# STM32F103.net
KiCad netlist of a schematic drawn in Altium Designer
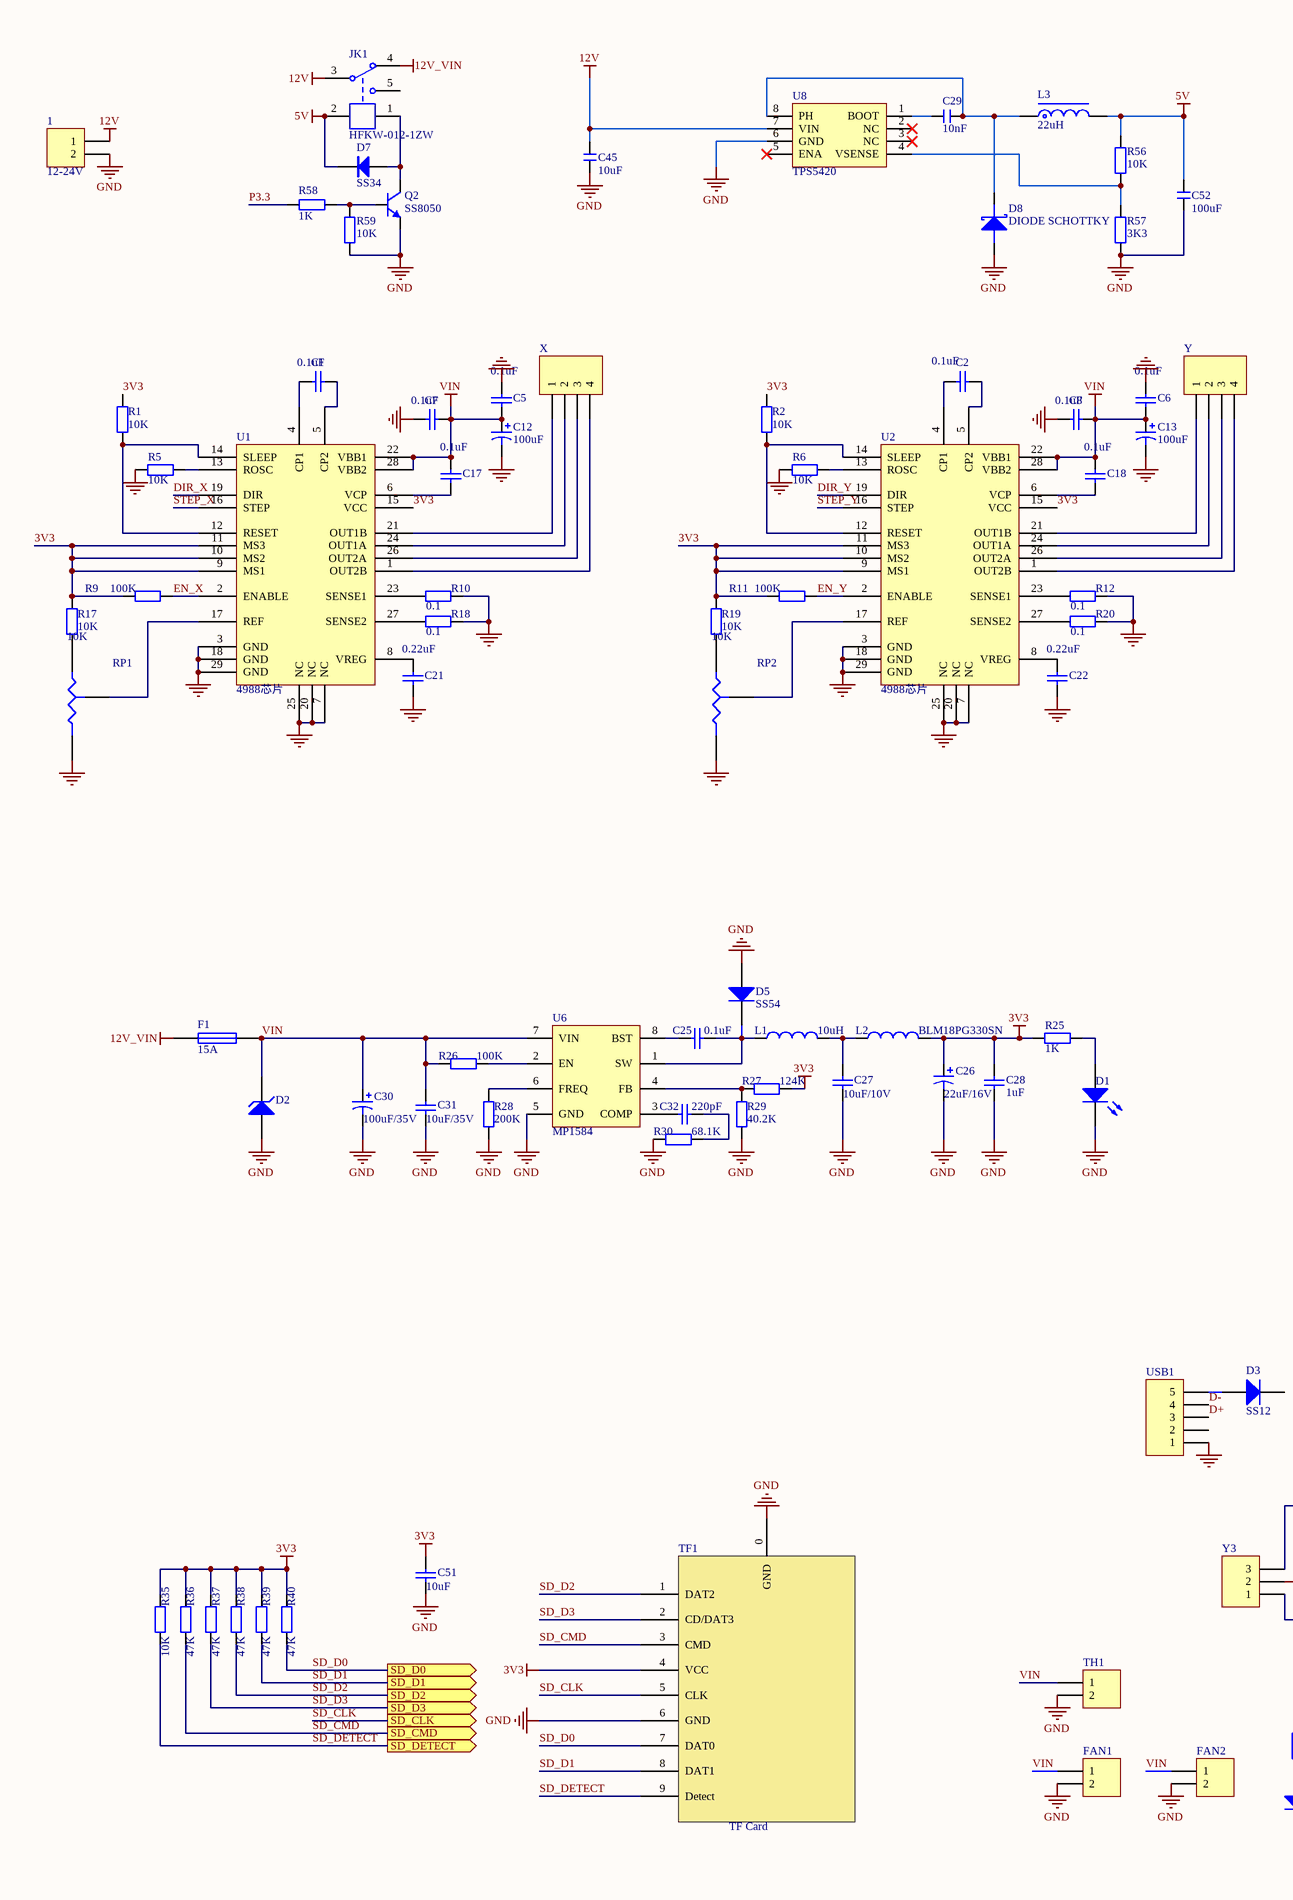
[diagram p0: STM32F103.SCHDOC, left]
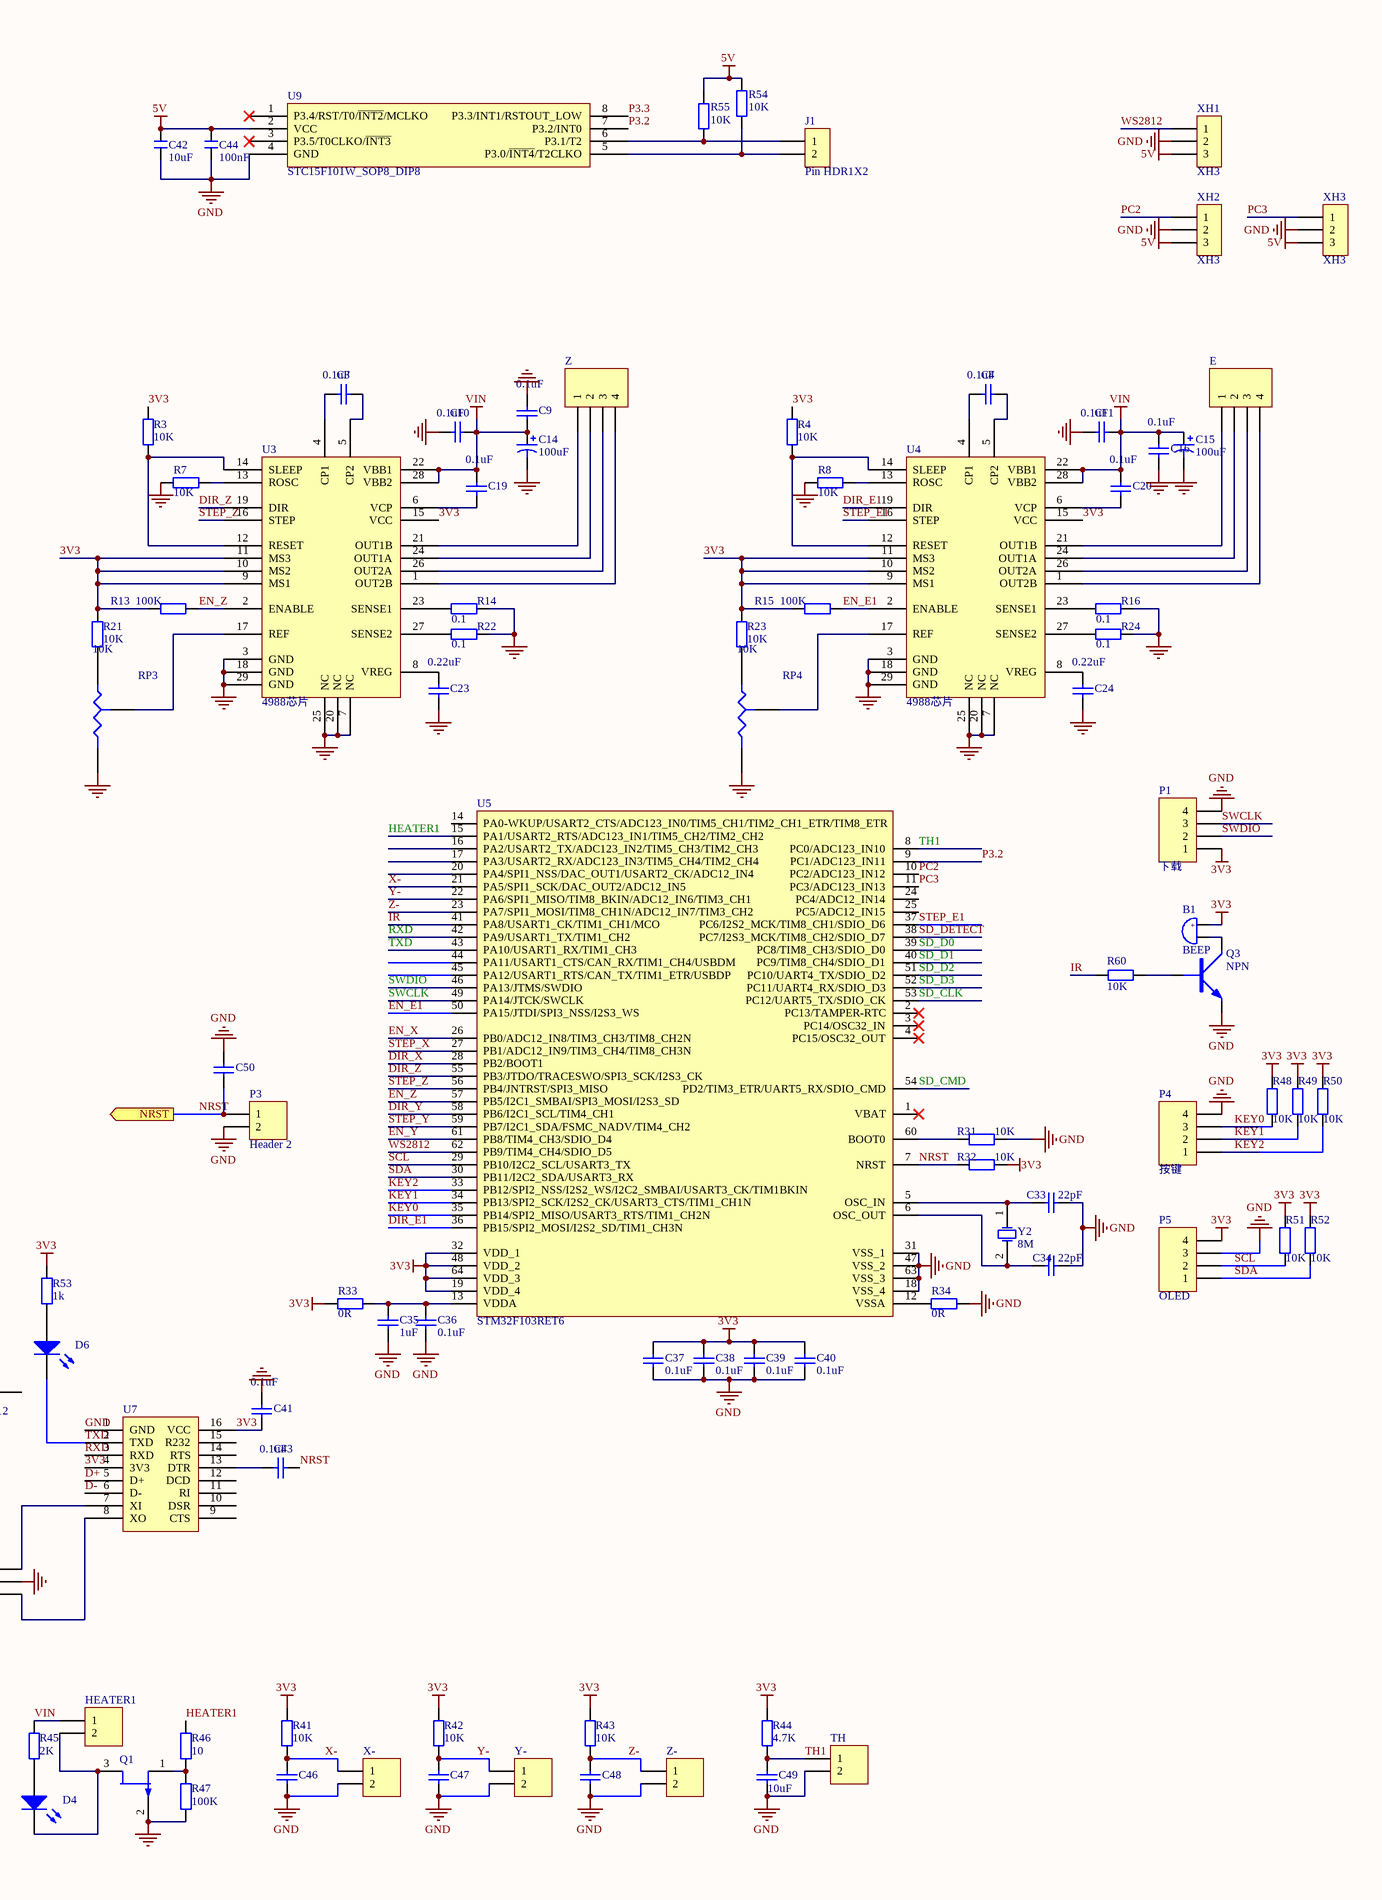
[diagram p1: STM32F103.SCHDOC, right]

(export (version "E")
  (design (tool "Eeschema 10.0.6"))
  (components
    (comp (ref "1")
      (value "12-24V")
      (footprint "VH-2P")
      (description "Header, 2-Pin")
      (fields (field (name "PUBLISHER") "Altium Limited"))
      (libsource (lib "") (part "Header 2_1"))
    )
    (comp (ref "B1")
      (value "BEEP")
      (footprint "BEEP 5x9x5.5")
      (description "蜂鸣器")
      (libsource (lib "蜂鸣器") (part "BEEP"))
    )
    (comp (ref "C1")
      (value "0.1uF")
      (footprint "0603")
      (description "Capacitor")
      (fields (field (name "Comment") "Cap") (field (name "PUBLISHER") "Altium Limited"))
      (libsource (lib "Miscellaneous Devices") (part "Cap"))
    )
    (comp (ref "C2")
      (value "0.1uF")
      (footprint "0603")
      (description "Capacitor")
      (fields (field (name "Comment") "Cap") (field (name "PUBLISHER") "Altium Limited"))
      (libsource (lib "Miscellaneous Devices") (part "Cap"))
    )
    (comp (ref "C3")
      (value "0.1uF")
      (footprint "0603")
      (description "Capacitor")
      (fields (field (name "Comment") "Cap") (field (name "PUBLISHER") "Altium Limited"))
      (libsource (lib "Miscellaneous Devices") (part "Cap"))
    )
    (comp (ref "C4")
      (value "0.1uF")
      (footprint "0603")
      (description "Capacitor")
      (fields (field (name "Comment") "Cap") (field (name "PUBLISHER") "Altium Limited"))
      (libsource (lib "Miscellaneous Devices") (part "Cap"))
    )
    (comp (ref "C5")
      (value "0.1uF")
      (footprint "0603")
      (description "Capacitor")
      (fields (field (name "Comment") "Cap") (field (name "PUBLISHER") "Altium Limited"))
      (libsource (lib "Miscellaneous Devices") (part "Cap"))
    )
    (comp (ref "C6")
      (value "0.1uF")
      (footprint "0603")
      (description "Capacitor")
      (fields (field (name "Comment") "Cap") (field (name "PUBLISHER") "Altium Limited"))
      (libsource (lib "Miscellaneous Devices") (part "Cap"))
    )
    (comp (ref "C7")
      (value "0.1uF")
      (footprint "0603")
      (description "Capacitor")
      (fields (field (name "Comment") "Cap") (field (name "PUBLISHER") "Altium Limited"))
      (libsource (lib "Miscellaneous Devices") (part "Cap"))
    )
    (comp (ref "C8")
      (value "0.1uF")
      (footprint "0603")
      (description "Capacitor")
      (fields (field (name "Comment") "Cap") (field (name "PUBLISHER") "Altium Limited"))
      (libsource (lib "Miscellaneous Devices") (part "Cap"))
    )
    (comp (ref "C9")
      (value "0.1uF")
      (footprint "0603")
      (description "Capacitor")
      (fields (field (name "Comment") "Cap") (field (name "PUBLISHER") "Altium Limited"))
      (libsource (lib "Miscellaneous Devices") (part "Cap"))
    )
    (comp (ref "C10")
      (value "0.1uF")
      (footprint "0603")
      (description "Capacitor")
      (fields (field (name "Comment") "Cap") (field (name "PUBLISHER") "Altium Limited"))
      (libsource (lib "Miscellaneous Devices") (part "Cap"))
    )
    (comp (ref "C11")
      (value "0.1uF")
      (footprint "0603")
      (description "Capacitor")
      (fields (field (name "Comment") "Cap") (field (name "PUBLISHER") "Altium Limited"))
      (libsource (lib "Miscellaneous Devices") (part "Cap"))
    )
    (comp (ref "C12")
      (value "100uF")
      (footprint "电容100nf35V")
      (description "Polarized Capacitor (Radial)")
      (fields (field (name "Comment") "Cap Pol1") (field (name "PUBLISHER") "Altium Limited"))
      (libsource (lib "Miscellaneous Devices") (part "Cap Pol1"))
    )
    (comp (ref "C13")
      (value "100uF")
      (footprint "电容100nf35V")
      (description "Polarized Capacitor (Radial)")
      (fields (field (name "Comment") "Cap Pol1") (field (name "PUBLISHER") "Altium Limited"))
      (libsource (lib "Miscellaneous Devices") (part "Cap Pol1"))
    )
    (comp (ref "C14")
      (value "100uF")
      (footprint "电容100nf35V")
      (description "Polarized Capacitor (Radial)")
      (fields (field (name "Comment") "Cap Pol1") (field (name "PUBLISHER") "Altium Limited"))
      (libsource (lib "Miscellaneous Devices") (part "Cap Pol1"))
    )
    (comp (ref "C15")
      (value "100uF")
      (footprint "电容100nf35V")
      (description "Polarized Capacitor (Radial)")
      (fields (field (name "Comment") "Cap Pol1") (field (name "PUBLISHER") "Altium Limited"))
      (libsource (lib "Miscellaneous Devices") (part "Cap Pol1"))
    )
    (comp (ref "C16")
      (value "0.1uF")
      (footprint "0603")
      (description "Capacitor")
      (fields (field (name "Comment") "Cap") (field (name "PUBLISHER") "Altium Limited"))
      (libsource (lib "Miscellaneous Devices") (part "Cap"))
    )
    (comp (ref "C17")
      (value "0.1uF")
      (footprint "0603")
      (description "Capacitor")
      (fields (field (name "Comment") "Cap") (field (name "PUBLISHER") "Altium Limited"))
      (libsource (lib "Miscellaneous Devices") (part "Cap"))
    )
    (comp (ref "C18")
      (value "0.1uF")
      (footprint "0603")
      (description "Capacitor")
      (fields (field (name "Comment") "Cap") (field (name "PUBLISHER") "Altium Limited"))
      (libsource (lib "Miscellaneous Devices") (part "Cap"))
    )
    (comp (ref "C19")
      (value "0.1uF")
      (footprint "0603")
      (description "Capacitor")
      (fields (field (name "Comment") "Cap") (field (name "PUBLISHER") "Altium Limited"))
      (libsource (lib "Miscellaneous Devices") (part "Cap"))
    )
    (comp (ref "C20")
      (value "0.1uF")
      (footprint "0603")
      (description "Capacitor")
      (fields (field (name "Comment") "Cap") (field (name "PUBLISHER") "Altium Limited"))
      (libsource (lib "Miscellaneous Devices") (part "Cap"))
    )
    (comp (ref "C21")
      (value "0.22uF")
      (footprint "0603")
      (description "Capacitor")
      (fields (field (name "Comment") "Cap") (field (name "PUBLISHER") "Altium Limited"))
      (libsource (lib "Miscellaneous Devices") (part "Cap"))
    )
    (comp (ref "C22")
      (value "0.22uF")
      (footprint "0603")
      (description "Capacitor")
      (fields (field (name "Comment") "Cap") (field (name "PUBLISHER") "Altium Limited"))
      (libsource (lib "Miscellaneous Devices") (part "Cap"))
    )
    (comp (ref "C23")
      (value "0.22uF")
      (footprint "0603")
      (description "Capacitor")
      (fields (field (name "Comment") "Cap") (field (name "PUBLISHER") "Altium Limited"))
      (libsource (lib "Miscellaneous Devices") (part "Cap"))
    )
    (comp (ref "C24")
      (value "0.22uF")
      (footprint "0603")
      (description "Capacitor")
      (fields (field (name "Comment") "Cap") (field (name "PUBLISHER") "Altium Limited"))
      (libsource (lib "Miscellaneous Devices") (part "Cap"))
    )
    (comp (ref "C25")
      (value "0.1uF")
      (footprint "0603")
      (description "Capacitor")
      (fields (field (name "Comment") "Cap") (field (name "PUBLISHER") "Altium Limited"))
      (libsource (lib "Miscellaneous Devices") (part "Cap"))
    )
    (comp (ref "C26")
      (value "22uF/16V")
      (footprint "TAN-A")
      (description "Polarized Capacitor (Radial)")
      (fields (field (name "Comment") "Cap Pol1") (field (name "PUBLISHER") "Altium Limited"))
      (libsource (lib "Miscellaneous Devices") (part "Cap Pol1"))
    )
    (comp (ref "C27")
      (value "10uF/10V")
      (footprint "0805")
      (description "Capacitor")
      (fields (field (name "Comment") "Cap") (field (name "PUBLISHER") "Altium Limited"))
      (libsource (lib "Miscellaneous Devices") (part "Cap"))
    )
    (comp (ref "C28")
      (value "1uF")
      (footprint "0603")
      (description "Capacitor")
      (fields (field (name "Comment") "Cap") (field (name "PUBLISHER") "Altium Limited"))
      (libsource (lib "Miscellaneous Devices") (part "Cap"))
    )
    (comp (ref "C29")
      (value "10nF")
      (footprint "C 0603_L")
      (description "无极性贴片电容")
      (libsource (lib "BEST") (part "C"))
    )
    (comp (ref "C30")
      (value "100uF/35V")
      (footprint "电容100nf35V")
      (description "Polarized Capacitor (Radial)")
      (fields (field (name "Comment") "Cap Pol1") (field (name "PUBLISHER") "Altium Limited"))
      (libsource (lib "Miscellaneous Devices") (part "Cap Pol1"))
    )
    (comp (ref "C31")
      (value "10uF/35V")
      (footprint "0805")
      (description "Capacitor")
      (fields (field (name "Comment") "Cap") (field (name "PUBLISHER") "Altium Limited"))
      (libsource (lib "Miscellaneous Devices") (part "Cap"))
    )
    (comp (ref "C32")
      (value "220pF")
      (footprint "0603")
      (description "Capacitor")
      (fields (field (name "Comment") "Cap") (field (name "PUBLISHER") "Altium Limited"))
      (libsource (lib "Miscellaneous Devices") (part "Cap"))
    )
    (comp (ref "C33")
      (value "22pF")
      (footprint "0603")
      (description "Capacitor")
      (fields (field (name "Comment") "Cap") (field (name "PUBLISHER") "Altium Limited"))
      (libsource (lib "Miscellaneous Devices") (part "Cap"))
    )
    (comp (ref "C34")
      (value "22pF")
      (footprint "0603")
      (description "Capacitor")
      (fields (field (name "Comment") "Cap") (field (name "PUBLISHER") "Altium Limited"))
      (libsource (lib "Miscellaneous Devices") (part "Cap"))
    )
    (comp (ref "C35")
      (value "1uF")
      (footprint "0603")
      (description "Capacitor")
      (fields (field (name "Comment") "Cap") (field (name "PUBLISHER") "Altium Limited"))
      (libsource (lib "Miscellaneous Devices") (part "Cap"))
    )
    (comp (ref "C36")
      (value "0.1uF")
      (footprint "0603")
      (description "Capacitor")
      (fields (field (name "Comment") "Cap") (field (name "PUBLISHER") "Altium Limited"))
      (libsource (lib "Miscellaneous Devices") (part "Cap"))
    )
    (comp (ref "C37")
      (value "0.1uF")
      (footprint "0603")
      (description "Capacitor")
      (fields (field (name "Comment") "Cap") (field (name "PUBLISHER") "Altium Limited"))
      (libsource (lib "Miscellaneous Devices") (part "Cap"))
    )
    (comp (ref "C38")
      (value "0.1uF")
      (footprint "0603")
      (description "Capacitor")
      (fields (field (name "Comment") "Cap") (field (name "PUBLISHER") "Altium Limited"))
      (libsource (lib "Miscellaneous Devices") (part "Cap"))
    )
    (comp (ref "C39")
      (value "0.1uF")
      (footprint "0603")
      (description "Capacitor")
      (fields (field (name "Comment") "Cap") (field (name "PUBLISHER") "Altium Limited"))
      (libsource (lib "Miscellaneous Devices") (part "Cap"))
    )
    (comp (ref "C40")
      (value "0.1uF")
      (footprint "0603")
      (description "Capacitor")
      (fields (field (name "Comment") "Cap") (field (name "PUBLISHER") "Altium Limited"))
      (libsource (lib "Miscellaneous Devices") (part "Cap"))
    )
    (comp (ref "C41")
      (value "0.1uF")
      (footprint "0603")
      (description "Capacitor")
      (fields (field (name "Comment") "Cap") (field (name "PUBLISHER") "Altium Limited"))
      (libsource (lib "Miscellaneous Devices") (part "Cap"))
    )
    (comp (ref "C42")
      (value "10uF")
      (footprint "C 0603_L")
      (description "无极性贴片电容")
      (libsource (lib "BEST") (part "C"))
    )
    (comp (ref "C43")
      (value "0.1uF")
      (footprint "0603")
      (description "Capacitor")
      (fields (field (name "Comment") "Cap") (field (name "PUBLISHER") "Altium Limited"))
      (libsource (lib "Miscellaneous Devices") (part "Cap"))
    )
    (comp (ref "C44")
      (value "100nF")
      (footprint "C 0603_L")
      (description "无极性贴片电容")
      (libsource (lib "BEST") (part "C"))
    )
    (comp (ref "C45")
      (value "10uF")
      (footprint "C 0603_L")
      (description "无极性贴片电容")
      (libsource (lib "BEST") (part "C"))
    )
    (comp (ref "C46")
      (value "Cap")
      (footprint "0603")
      (description "Capacitor")
      (fields (field (name "PUBLISHER") "Altium Limited"))
      (libsource (lib "Miscellaneous Devices") (part "Cap"))
    )
    (comp (ref "C47")
      (value "Cap")
      (footprint "0603")
      (description "Capacitor")
      (fields (field (name "PUBLISHER") "Altium Limited"))
      (libsource (lib "Miscellaneous Devices") (part "Cap"))
    )
    (comp (ref "C48")
      (value "Cap")
      (footprint "0603")
      (description "Capacitor")
      (fields (field (name "PUBLISHER") "Altium Limited"))
      (libsource (lib "Miscellaneous Devices") (part "Cap"))
    )
    (comp (ref "C49")
      (value "10uF")
      (footprint "0805")
      (description "Capacitor")
      (fields (field (name "Comment") "Cap") (field (name "PUBLISHER") "Altium Limited"))
      (libsource (lib "Miscellaneous Devices") (part "Cap"))
    )
    (comp (ref "C50")
      (value "Cap")
      (footprint "0603")
      (description "Capacitor")
      (fields (field (name "PUBLISHER") "Altium Limited"))
      (libsource (lib "Miscellaneous Devices") (part "Cap"))
    )
    (comp (ref "C51")
      (value "10uF")
      (footprint "0805")
      (description "Capacitor")
      (fields (field (name "Comment") "Cap") (field (name "PUBLISHER") "Altium Limited"))
      (libsource (lib "Miscellaneous Devices") (part "Cap"))
    )
    (comp (ref "C52")
      (value "100uF")
      (footprint "C 0805_L")
      (description "无极性贴片电容")
      (libsource (lib "BEST") (part "C"))
    )
    (comp (ref "D1")
      (value "LED1")
      (footprint "LED-0603贴片")
      (description "Typical RED GaAs LED")
      (fields (field (name "PUBLISHER") "Altium Limited"))
      (libsource (lib "Miscellaneous Devices") (part "LED1"))
    )
    (comp (ref "D2")
      (value "SMAJ33A")
      (footprint "SMA - duplicate")
      (description "Zener Diode")
      (fields (field (name "PUBLISHER") "Altium Limited"))
      (libsource (lib "Miscellaneous Devices") (part "D Zener"))
    )
    (comp (ref "D3")
      (value "SS12")
      (footprint "SMA - duplicate")
      (description "High Conductance Fast Diode")
      (fields (field (name "PUBLISHER") "Altium Limited"))
      (libsource (lib "Miscellaneous Devices") (part "Diode 1N914"))
    )
    (comp (ref "D4")
      (value "LED2")
      (footprint "LED-0603贴片")
      (description "Typical RED, GREEN, YELLOW, AMBER GaAs LED")
      (fields (field (name "PUBLISHER") "Altium Limited"))
      (libsource (lib "Miscellaneous Devices") (part "LED2"))
    )
    (comp (ref "D5")
      (value "SS54")
      (footprint "SMA - duplicate")
      (description "1 Amp General Purpose Rectifier")
      (fields (field (name "PUBLISHER") "Altium Limited"))
      (libsource (lib "Miscellaneous Devices") (part "Diode 1N4001"))
    )
    (comp (ref "D6")
      (value "LED2")
      (footprint "LED-0603贴片")
      (description "Typical RED, GREEN, YELLOW, AMBER GaAs LED")
      (fields (field (name "PUBLISHER") "Altium Limited"))
      (libsource (lib "Miscellaneous Devices") (part "LED2"))
    )
    (comp (ref "D7")
      (value "SS34")
      (footprint "SMB")
      (description "肖特基二极管")
      (fields (field (name "版权归属") "源创客"))
      (libsource (lib "BEST") (part "SS24"))
    )
    (comp (ref "D8")
      (value "DIODE SCHOTTKY")
      (footprint "SOD-123")
      (description "肖特基二极管")
      (libsource (lib "二极管") (part "DIODE SCHOTTKY"))
    )
    (comp (ref "E")
      (value "MHDR1X4")
      (footprint "2.54mm4pin")
      (description "Header, 4-Pin")
      (fields (field (name "PUBLISHER") "Altium Limited"))
      (libsource (lib "Miscellaneous Connectors") (part "MHDR1X4"))
    )
    (comp (ref "F1")
      (value "15A")
      (footprint "1206")
      (description "Fuse")
      (fields (field (name "PUBLISHER") "Altium Limited"))
      (libsource (lib "Miscellaneous Devices") (part "Fuse 1"))
    )
    (comp (ref "FAN1")
      (value "Header 2")
      (footprint "2.54mm2pin")
      (description "Header, 2-Pin")
      (fields (field (name "PUBLISHER") "Altium Limited"))
      (libsource (lib "Miscellaneous Connectors") (part "Header 2"))
    )
    (comp (ref "FAN2")
      (value "Header 2")
      (footprint "2.54mm2pin")
      (description "Header, 2-Pin")
      (fields (field (name "PUBLISHER") "Altium Limited"))
      (libsource (lib "Miscellaneous Connectors") (part "Header 2"))
    )
    (comp (ref "HEATER1")
      (value "Header 2")
      (footprint "VH-2P")
      (description "Header, 2-Pin")
      (fields (field (name "PUBLISHER") "Altium Limited"))
      (libsource (lib "Miscellaneous Connectors") (part "Header 2"))
    )
    (comp (ref "J1")
      (value "Pin HDR1X2")
      (footprint "Pin HDR1X2/2.54mm-S")
      (libsource (lib "排针") (part "Pin HDR1X2"))
    )
    (comp (ref "JK1")
      (value "HFKW-012-1ZW")
      (footprint "012-1ZW_W")
      (description "12V一组转换")
      (fields (field (name "版权归属") "源创客"))
      (libsource (lib "继电器") (part "HFKW-012-1ZW"))
    )
    (comp (ref "L1")
      (value "10uH")
      (footprint "5*5mm")
      (description "Inductor")
      (fields (field (name "PUBLISHER") "Altium Limited"))
      (libsource (lib "Miscellaneous Devices") (part "Inductor"))
    )
    (comp (ref "L2")
      (value "BLM18PG330SN")
      (footprint "0603")
      (description "Inductor")
      (fields (field (name "PUBLISHER") "Altium Limited"))
      (libsource (lib "Miscellaneous Devices") (part "Inductor"))
    )
    (comp (ref "L3")
      (value "22uH")
      (footprint "CD54")
      (description "贴片功率电感")
      (fields (field (name "版权归属") "源创客"))
      (libsource (lib "BEST") (part "L-CD"))
    )
    (comp (ref "P1")
      (value "下载")
      (footprint "HDR1X4")
      (description "Header, 4-Pin")
      (fields (field (name "PUBLISHER") "Altium Limited"))
      (libsource (lib "Miscellaneous Connectors") (part "Header 4"))
    )
    (comp (ref "P3")
      (value "Header 2")
      (footprint "HDR1X2")
      (description "Header, 2-Pin")
      (fields (field (name "PUBLISHER") "Altium Limited"))
      (libsource (lib "Miscellaneous Connectors") (part "Header 2"))
    )
    (comp (ref "P4")
      (value "按键")
      (footprint "2.54mm4pin")
      (description "Header, 4-Pin")
      (fields (field (name "PUBLISHER") "Altium Limited"))
      (libsource (lib "Miscellaneous Connectors") (part "Header 4"))
    )
    (comp (ref "P5")
      (value "OLED")
      (footprint "2.54mm4pin")
      (description "Header, 4-Pin")
      (fields (field (name "PUBLISHER") "Altium Limited"))
      (libsource (lib "Miscellaneous Connectors") (part "Header 4"))
    )
    (comp (ref "Q1")
      (value "JFET-P")
      (footprint "加热控制")
      (description "P-Channel JFET")
      (fields (field (name "PUBLISHER") "Altium Limited"))
      (libsource (lib "Miscellaneous Devices") (part "JFET-P"))
    )
    (comp (ref "Q2")
      (value "SS8050")
      (footprint "SOT23-3N")
      (description "高频放大-NPN型")
      (fields (field (name "版权归属") "源创客"))
      (libsource (lib "BEST") (part "8050-SMD"))
    )
    (comp (ref "Q3")
      (value "NPN")
      (footprint "SOT-23")
      (description "NPN三极管")
      (libsource (lib "三极管") (part "NPN"))
    )
    (comp (ref "R1")
      (value "10K")
      (footprint "0603")
      (description "Resistor")
      (fields (field (name "Comment") "Res2") (field (name "PUBLISHER") "Altium Limited"))
      (libsource (lib "") (part "Res2_2"))
    )
    (comp (ref "R2")
      (value "10K")
      (footprint "0603")
      (description "Resistor")
      (fields (field (name "Comment") "Res2") (field (name "PUBLISHER") "Altium Limited"))
      (libsource (lib "") (part "Res2_2"))
    )
    (comp (ref "R3")
      (value "10K")
      (footprint "0603")
      (description "Resistor")
      (fields (field (name "Comment") "Res2") (field (name "PUBLISHER") "Altium Limited"))
      (libsource (lib "") (part "Res2_2"))
    )
    (comp (ref "R4")
      (value "10K")
      (footprint "0603")
      (description "Resistor")
      (fields (field (name "Comment") "Res2") (field (name "PUBLISHER") "Altium Limited"))
      (libsource (lib "") (part "Res2_2"))
    )
    (comp (ref "R5")
      (value "10K")
      (footprint "0603")
      (description "Resistor")
      (fields (field (name "Comment") "Res2") (field (name "PUBLISHER") "Altium Limited"))
      (libsource (lib "") (part "Res2_3"))
    )
    (comp (ref "R6")
      (value "10K")
      (footprint "0603")
      (description "Resistor")
      (fields (field (name "Comment") "Res2") (field (name "PUBLISHER") "Altium Limited"))
      (libsource (lib "") (part "Res2_3"))
    )
    (comp (ref "R7")
      (value "10K")
      (footprint "0603")
      (description "Resistor")
      (fields (field (name "Comment") "Res2") (field (name "PUBLISHER") "Altium Limited"))
      (libsource (lib "") (part "Res2_3"))
    )
    (comp (ref "R8")
      (value "10K")
      (footprint "0603")
      (description "Resistor")
      (fields (field (name "Comment") "Res2") (field (name "PUBLISHER") "Altium Limited"))
      (libsource (lib "") (part "Res2_3"))
    )
    (comp (ref "R9")
      (value "100K")
      (footprint "0603")
      (description "Resistor")
      (fields (field (name "Comment") "Res2") (field (name "PUBLISHER") "Altium Limited"))
      (libsource (lib "") (part "Res2_3"))
    )
    (comp (ref "R10")
      (value "0.1")
      (footprint "0805")
      (description "Resistor")
      (fields (field (name "Comment") "Res2") (field (name "PUBLISHER") "Altium Limited"))
      (libsource (lib "") (part "Res2_1"))
    )
    (comp (ref "R11")
      (value "100K")
      (footprint "0603")
      (description "Resistor")
      (fields (field (name "Comment") "Res2") (field (name "PUBLISHER") "Altium Limited"))
      (libsource (lib "") (part "Res2_3"))
    )
    (comp (ref "R12")
      (value "0.1")
      (footprint "0805")
      (description "Resistor")
      (fields (field (name "Comment") "Res2") (field (name "PUBLISHER") "Altium Limited"))
      (libsource (lib "") (part "Res2_1"))
    )
    (comp (ref "R13")
      (value "100K")
      (footprint "0603")
      (description "Resistor")
      (fields (field (name "Comment") "Res2") (field (name "PUBLISHER") "Altium Limited"))
      (libsource (lib "") (part "Res2_3"))
    )
    (comp (ref "R14")
      (value "0.1")
      (footprint "0805")
      (description "Resistor")
      (fields (field (name "Comment") "Res2") (field (name "PUBLISHER") "Altium Limited"))
      (libsource (lib "") (part "Res2_1"))
    )
    (comp (ref "R15")
      (value "100K")
      (footprint "0603")
      (description "Resistor")
      (fields (field (name "Comment") "Res2") (field (name "PUBLISHER") "Altium Limited"))
      (libsource (lib "") (part "Res2_3"))
    )
    (comp (ref "R16")
      (value "0.1")
      (footprint "0805")
      (description "Resistor")
      (fields (field (name "Comment") "Res2") (field (name "PUBLISHER") "Altium Limited"))
      (libsource (lib "") (part "Res2_1"))
    )
    (comp (ref "R17")
      (value "10K")
      (footprint "0603")
      (description "Resistor")
      (fields (field (name "Comment") "Res2") (field (name "PUBLISHER") "Altium Limited"))
      (libsource (lib "Miscellaneous Devices") (part "Res2"))
    )
    (comp (ref "R18")
      (value "0.1")
      (footprint "0805")
      (description "Resistor")
      (fields (field (name "Comment") "Res2") (field (name "PUBLISHER") "Altium Limited"))
      (libsource (lib "") (part "Res2_1"))
    )
    (comp (ref "R19")
      (value "10K")
      (footprint "0603")
      (description "Resistor")
      (fields (field (name "Comment") "Res2") (field (name "PUBLISHER") "Altium Limited"))
      (libsource (lib "Miscellaneous Devices") (part "Res2"))
    )
    (comp (ref "R20")
      (value "0.1")
      (footprint "0805")
      (description "Resistor")
      (fields (field (name "Comment") "Res2") (field (name "PUBLISHER") "Altium Limited"))
      (libsource (lib "") (part "Res2_1"))
    )
    (comp (ref "R21")
      (value "10K")
      (footprint "0603")
      (description "Resistor")
      (fields (field (name "Comment") "Res2") (field (name "PUBLISHER") "Altium Limited"))
      (libsource (lib "Miscellaneous Devices") (part "Res2"))
    )
    (comp (ref "R22")
      (value "0.1")
      (footprint "0805")
      (description "Resistor")
      (fields (field (name "Comment") "Res2") (field (name "PUBLISHER") "Altium Limited"))
      (libsource (lib "") (part "Res2_1"))
    )
    (comp (ref "R23")
      (value "10K")
      (footprint "0603")
      (description "Resistor")
      (fields (field (name "Comment") "Res2") (field (name "PUBLISHER") "Altium Limited"))
      (libsource (lib "Miscellaneous Devices") (part "Res2"))
    )
    (comp (ref "R24")
      (value "0.1")
      (footprint "0805")
      (description "Resistor")
      (fields (field (name "Comment") "Res2") (field (name "PUBLISHER") "Altium Limited"))
      (libsource (lib "") (part "Res2_1"))
    )
    (comp (ref "R25")
      (value "1K")
      (footprint "0603")
      (description "Resistor")
      (fields (field (name "Comment") "Res2") (field (name "PUBLISHER") "Altium Limited"))
      (libsource (lib "") (part "Res2_3"))
    )
    (comp (ref "R26")
      (value "100K")
      (footprint "0603")
      (description "Resistor")
      (fields (field (name "Comment") "Res2") (field (name "PUBLISHER") "Altium Limited"))
      (libsource (lib "") (part "Res2_2"))
    )
    (comp (ref "R27")
      (value "124K")
      (footprint "0603")
      (description "Resistor")
      (fields (field (name "Comment") "Res2") (field (name "PUBLISHER") "Altium Limited"))
      (libsource (lib "") (part "Res2_2"))
    )
    (comp (ref "R28")
      (value "200K")
      (footprint "0603")
      (description "Resistor")
      (fields (field (name "Comment") "Res2") (field (name "PUBLISHER") "Altium Limited"))
      (libsource (lib "") (part "Res2_1"))
    )
    (comp (ref "R29")
      (value "40.2K")
      (footprint "0603")
      (description "Resistor")
      (fields (field (name "Comment") "Res2") (field (name "PUBLISHER") "Altium Limited"))
      (libsource (lib "") (part "Res2_1"))
    )
    (comp (ref "R30")
      (value "68.1K")
      (footprint "0603")
      (description "Resistor")
      (fields (field (name "Comment") "Res2") (field (name "PUBLISHER") "Altium Limited"))
      (libsource (lib "Miscellaneous Devices") (part "Res2"))
    )
    (comp (ref "R31")
      (value "10K")
      (footprint "0603")
      (description "Resistor")
      (fields (field (name "Comment") "Res2") (field (name "PUBLISHER") "Altium Limited"))
      (libsource (lib "") (part "Res2_2"))
    )
    (comp (ref "R32")
      (value "10K")
      (footprint "0603")
      (description "Resistor")
      (fields (field (name "Comment") "Res2") (field (name "PUBLISHER") "Altium Limited"))
      (libsource (lib "") (part "Res2_2"))
    )
    (comp (ref "R33")
      (value "0R")
      (footprint "0603")
      (description "Resistor")
      (fields (field (name "Comment") "Res2") (field (name "PUBLISHER") "Altium Limited"))
      (libsource (lib "") (part "Res2_3"))
    )
    (comp (ref "R34")
      (value "0R")
      (footprint "0603")
      (description "Resistor")
      (fields (field (name "Comment") "Res2") (field (name "PUBLISHER") "Altium Limited"))
      (libsource (lib "") (part "Res2_3"))
    )
    (comp (ref "R35")
      (value "10K")
      (footprint "0603")
      (description "Resistor")
      (fields (field (name "Comment") "Res2") (field (name "PUBLISHER") "Altium Limited"))
      (libsource (lib "Miscellaneous Devices") (part "Res2"))
    )
    (comp (ref "R36")
      (value "47K")
      (footprint "0603")
      (description "Resistor")
      (fields (field (name "Comment") "Res2") (field (name "PUBLISHER") "Altium Limited"))
      (libsource (lib "Miscellaneous Devices") (part "Res2"))
    )
    (comp (ref "R37")
      (value "47K")
      (footprint "0603")
      (description "Resistor")
      (fields (field (name "Comment") "Res2") (field (name "PUBLISHER") "Altium Limited"))
      (libsource (lib "Miscellaneous Devices") (part "Res2"))
    )
    (comp (ref "R38")
      (value "47K")
      (footprint "0603")
      (description "Resistor")
      (fields (field (name "Comment") "Res2") (field (name "PUBLISHER") "Altium Limited"))
      (libsource (lib "Miscellaneous Devices") (part "Res2"))
    )
    (comp (ref "R39")
      (value "47K")
      (footprint "0603")
      (description "Resistor")
      (fields (field (name "Comment") "Res2") (field (name "PUBLISHER") "Altium Limited"))
      (libsource (lib "Miscellaneous Devices") (part "Res2"))
    )
    (comp (ref "R40")
      (value "47K")
      (footprint "0603")
      (description "Resistor")
      (fields (field (name "Comment") "Res2") (field (name "PUBLISHER") "Altium Limited"))
      (libsource (lib "Miscellaneous Devices") (part "Res2"))
    )
    (comp (ref "R41")
      (value "10K")
      (footprint "0603")
      (description "Resistor")
      (fields (field (name "Comment") "Res2") (field (name "PUBLISHER") "Altium Limited"))
      (libsource (lib "") (part "Res2_2"))
    )
    (comp (ref "R42")
      (value "10K")
      (footprint "0603")
      (description "Resistor")
      (fields (field (name "Comment") "Res2") (field (name "PUBLISHER") "Altium Limited"))
      (libsource (lib "") (part "Res2_2"))
    )
    (comp (ref "R43")
      (value "10K")
      (footprint "0603")
      (description "Resistor")
      (fields (field (name "Comment") "Res2") (field (name "PUBLISHER") "Altium Limited"))
      (libsource (lib "") (part "Res2_2"))
    )
    (comp (ref "R44")
      (value "4.7K")
      (footprint "0603")
      (description "Resistor")
      (fields (field (name "Comment") "Res2") (field (name "PUBLISHER") "Altium Limited"))
      (libsource (lib "Miscellaneous Devices") (part "Res2"))
    )
    (comp (ref "R45")
      (value "2K")
      (footprint "0603")
      (description "Resistor")
      (fields (field (name "Comment") "Res2") (field (name "PUBLISHER") "Altium Limited"))
      (libsource (lib "Miscellaneous Devices") (part "Res2"))
    )
    (comp (ref "R46")
      (value "10")
      (footprint "0603")
      (description "Resistor")
      (fields (field (name "Comment") "Res2") (field (name "PUBLISHER") "Altium Limited"))
      (libsource (lib "Miscellaneous Devices") (part "Res2"))
    )
    (comp (ref "R47")
      (value "100K")
      (footprint "0603")
      (description "Resistor")
      (fields (field (name "Comment") "Res2") (field (name "PUBLISHER") "Altium Limited"))
      (libsource (lib "Miscellaneous Devices") (part "Res2"))
    )
    (comp (ref "R48")
      (value "10K")
      (footprint "0603")
      (description "Resistor")
      (fields (field (name "Comment") "Res2") (field (name "PUBLISHER") "Altium Limited"))
      (libsource (lib "") (part "Res2_2"))
    )
    (comp (ref "R49")
      (value "10K")
      (footprint "0603")
      (description "Resistor")
      (fields (field (name "Comment") "Res2") (field (name "PUBLISHER") "Altium Limited"))
      (libsource (lib "") (part "Res2_2"))
    )
    (comp (ref "R50")
      (value "10K")
      (footprint "0603")
      (description "Resistor")
      (fields (field (name "Comment") "Res2") (field (name "PUBLISHER") "Altium Limited"))
      (libsource (lib "") (part "Res2_2"))
    )
    (comp (ref "R51")
      (value "10K")
      (footprint "0603")
      (description "Resistor")
      (fields (field (name "Comment") "Res2") (field (name "PUBLISHER") "Altium Limited"))
      (libsource (lib "") (part "Res2_2"))
    )
    (comp (ref "R52")
      (value "10K")
      (footprint "0603")
      (description "Resistor")
      (fields (field (name "Comment") "Res2") (field (name "PUBLISHER") "Altium Limited"))
      (libsource (lib "") (part "Res2_2"))
    )
    (comp (ref "R53")
      (value "1k")
      (footprint "0603")
      (description "Resistor")
      (fields (field (name "Comment") "Res2") (field (name "PUBLISHER") "Altium Limited"))
      (libsource (lib "Miscellaneous Devices") (part "Res2"))
    )
    (comp (ref "R54")
      (value "10K")
      (footprint "R 0603_L")
      (description "贴片电阻")
      (fields (field (name "版权归属") "源创客"))
      (libsource (lib "BEST") (part "R"))
    )
    (comp (ref "R55")
      (value "10K")
      (footprint "R 0603_L")
      (description "贴片电阻")
      (fields (field (name "版权归属") "源创客"))
      (libsource (lib "BEST") (part "R"))
    )
    (comp (ref "R56")
      (value "10K")
      (footprint "R 0603_L")
      (description "贴片电阻")
      (fields (field (name "版权归属") "源创客"))
      (libsource (lib "BEST") (part "R"))
    )
    (comp (ref "R57")
      (value "3K3")
      (footprint "R 0603_M")
      (description "贴片电阻")
      (fields (field (name "版权归属") "源创客"))
      (libsource (lib "BEST") (part "R"))
    )
    (comp (ref "R58")
      (value "1K")
      (footprint "R 0603_L")
      (description "贴片电阻")
      (fields (field (name "版权归属") "源创客"))
      (libsource (lib "BEST") (part "R"))
    )
    (comp (ref "R59")
      (value "10K")
      (footprint "R 0603_L")
      (description "贴片电阻")
      (fields (field (name "版权归属") "源创客"))
      (libsource (lib "BEST") (part "R"))
    )
    (comp (ref "R60")
      (value "10K")
      (footprint "R 0603_L")
      (description "贴片电阻")
      (fields (field (name "版权归属") "源创客"))
      (libsource (lib "BEST") (part "R"))
    )
    (comp (ref "RP1")
      (value "10K")
      (footprint "贴片可调电阻")
      (description "Tapped Resistor")
      (fields (field (name "Comment") "Res Tap") (field (name "PUBLISHER") "Altium Limited"))
      (libsource (lib "Miscellaneous Devices") (part "Res Tap"))
    )
    (comp (ref "RP2")
      (value "10K")
      (footprint "贴片可调电阻")
      (description "Tapped Resistor")
      (fields (field (name "Comment") "Res Tap") (field (name "PUBLISHER") "Altium Limited"))
      (libsource (lib "Miscellaneous Devices") (part "Res Tap"))
    )
    (comp (ref "RP3")
      (value "10K")
      (footprint "贴片可调电阻")
      (description "Tapped Resistor")
      (fields (field (name "Comment") "Res Tap") (field (name "PUBLISHER") "Altium Limited"))
      (libsource (lib "Miscellaneous Devices") (part "Res Tap"))
    )
    (comp (ref "RP4")
      (value "10K")
      (footprint "贴片可调电阻")
      (description "Tapped Resistor")
      (fields (field (name "Comment") "Res Tap") (field (name "PUBLISHER") "Altium Limited"))
      (libsource (lib "Miscellaneous Devices") (part "Res Tap"))
    )
    (comp (ref "TF1") (value "TF Card") (footprint "TF Card") (libsource (lib "*") (part "TF Card")))
    (comp (ref "TH")
      (value "Header 2")
      (footprint "2.54mm2pin")
      (description "Header, 2-Pin")
      (fields (field (name "PUBLISHER") "Altium Limited"))
      (libsource (lib "Miscellaneous Connectors") (part "Header 2"))
    )
    (comp (ref "TH1")
      (value "Header 2")
      (footprint "2.54mm2pin")
      (description "Header, 2-Pin")
      (fields (field (name "PUBLISHER") "Altium Limited"))
      (libsource (lib "STM32F103") (part "Header 2"))
    )
    (comp (ref "U1") (value "4988芯片") (footprint "4988芯片") (libsource (lib "*") (part "4988芯片")))
    (comp (ref "U2") (value "4988芯片") (footprint "4988芯片") (libsource (lib "*") (part "4988芯片")))
    (comp (ref "U3") (value "4988芯片") (footprint "4988芯片") (libsource (lib "*") (part "4988芯片")))
    (comp (ref "U4") (value "4988芯片") (footprint "4988芯片") (libsource (lib "*") (part "4988芯片")))
    (comp (ref "U5")
      (value "STM32F103RET6")
      (footprint "LQFP-64")
      (libsource (lib "Creality3D_F103RE") (part "STM32F103RET6"))
    )
    (comp (ref "U6")
      (value "MP1584")
      (footprint "SOP8+1")
      (libsource (lib "Creality3D_F103RE") (part "MP1584"))
    )
    (comp (ref "U7") (value "CH340G") (footprint "MSOP-16") (libsource (lib "*") (part "CH340G")))
    (comp (ref "U8")
      (value "TPS5420")
      (footprint "SOP8_M")
      (description "同步降压IC")
      (libsource (lib "BEST") (part "TPS5420"))
    )
    (comp (ref "U9")
      (value "STC15F101W_SOP8_DIP8")
      (footprint "SOP8")
      (libsource (lib "STC系列芯片") (part "STC15F101W_SOP8_DIP8"))
    )
    (comp (ref "USB1")
      (value "Header 5")
      (footprint "USB接口")
      (description "Header, 5-Pin")
      (fields (field (name "PUBLISHER") "Altium Limited"))
      (libsource (lib "Miscellaneous Connectors") (part "Header 5"))
    )
    (comp (ref "X")
      (value "MHDR1X4")
      (footprint "2.54mm4pin")
      (description "Header, 4-Pin")
      (fields (field (name "PUBLISHER") "Altium Limited"))
      (libsource (lib "Miscellaneous Connectors") (part "MHDR1X4"))
    )
    (comp (ref "X-")
      (value "Header 2")
      (footprint "2.54mm2pin")
      (description "Header, 2-Pin")
      (fields (field (name "PUBLISHER") "Altium Limited"))
      (libsource (lib "Miscellaneous Connectors") (part "Header 2"))
    )
    (comp (ref "XH1") (value "XH3") (footprint "XH3/2.54mm/180") (libsource (lib "XH，VH") (part "XH3")))
    (comp (ref "XH2") (value "XH3") (footprint "XH3/2.54mm/180") (libsource (lib "XH，VH") (part "XH3")))
    (comp (ref "XH3") (value "XH3") (footprint "XH3/2.54mm/180") (libsource (lib "XH，VH") (part "XH3")))
    (comp (ref "Y")
      (value "MHDR1X4")
      (footprint "2.54mm4pin")
      (description "Header, 4-Pin")
      (fields (field (name "PUBLISHER") "Altium Limited"))
      (libsource (lib "Miscellaneous Connectors") (part "MHDR1X4"))
    )
    (comp (ref "Y-")
      (value "Header 2")
      (footprint "2.54mm2pin")
      (description "Header, 2-Pin")
      (fields (field (name "PUBLISHER") "Altium Limited"))
      (libsource (lib "Miscellaneous Connectors") (part "Header 2"))
    )
    (comp (ref "Y2")
      (value "8M")
      (footprint "5032-2P")
      (description "Crystal Oscillator")
      (fields (field (name "PUBLISHER") "Altium Limited"))
      (libsource (lib "Miscellaneous Devices") (part "XTAL"))
    )
    (comp (ref "Y3")
      (value "Header 3H")
      (footprint "三脚晶振")
      (description "Header, 3-Pin, Right Angle")
      (fields (field (name "PUBLISHER") "Altium Limited"))
      (libsource (lib "Miscellaneous Connectors") (part "Header 3H"))
    )
    (comp (ref "Z")
      (value "MHDR1X4")
      (footprint "2.54mm4pin")
      (description "Header, 4-Pin")
      (fields (field (name "PUBLISHER") "Altium Limited"))
      (libsource (lib "Miscellaneous Connectors") (part "MHDR1X4"))
    )
    (comp (ref "Z-")
      (value "Header 2")
      (footprint "2.54mm2pin")
      (description "Header, 2-Pin")
      (fields (field (name "PUBLISHER") "Altium Limited"))
      (libsource (lib "Miscellaneous Connectors") (part "Header 2"))
    )
  )
  (nets
    (net (code "1") (name "/D+") (class "Default")
      (node (ref "U7") (pin "5") (pinfunction "D+_5") (pintype "open_collector"))
      (node (ref "USB1") (pin "3") (pinfunction "3_3") (pintype "passive"))
    )
    (net (code "2") (name "/D-") (class "Default")
      (node (ref "U7") (pin "6") (pinfunction "D-_6") (pintype "open_collector"))
      (node (ref "USB1") (pin "4") (pinfunction "4_4") (pintype "passive"))
    )
    (net (code "3") (name "/DIR_E1") (class "Default")
      (node (ref "U4") (pin "19") (pinfunction "DIR_19") (pintype "open_collector"))
      (node (ref "U5") (pin "36") (pinfunction "PB15/SPI2_MOSI/I2S2_SD/TIM1_CH3N_36") (pintype "passive"))
    )
    (net (code "4") (name "/DIR_X") (class "Default")
      (node (ref "U1") (pin "19") (pinfunction "DIR_19") (pintype "open_collector"))
      (node (ref "U5") (pin "28") (pinfunction "PB2/BOOT1_28") (pintype "passive"))
    )
    (net (code "5") (name "/DIR_Y") (class "Default")
      (node (ref "U2") (pin "19") (pinfunction "DIR_19") (pintype "open_collector"))
      (node (ref "U5") (pin "58") (pinfunction "PB6/I2C1_SCL/TIM4_CH1_58") (pintype "passive"))
    )
    (net (code "6") (name "/DIR_Z") (class "Default")
      (node (ref "U3") (pin "19") (pinfunction "DIR_19") (pintype "open_collector"))
      (node (ref "U5") (pin "55") (pinfunction "PB3/JTDO/TRACESWO/SPI3_SCK/I2S3_CK_55") (pintype "passive"))
    )
    (net (code "7") (name "/EN_E1") (class "Default")
      (node (ref "R15") (pin "1") (pinfunction "1_1") (pintype "passive"))
      (node (ref "U4") (pin "2") (pinfunction "ENABLE_2") (pintype "open_collector"))
      (node (ref "U5") (pin "50") (pinfunction "PA15/JTDI/SPI3_NSS/I2S3_WS_50") (pintype "passive"))
    )
    (net (code "8") (name "/EN_X") (class "Default")
      (node (ref "R9") (pin "1") (pinfunction "1_1") (pintype "passive"))
      (node (ref "U1") (pin "2") (pinfunction "ENABLE_2") (pintype "open_collector"))
      (node (ref "U5") (pin "26") (pinfunction "PB0/ADC12_IN8/TIM3_CH3/TIM8_CH2N_26") (pintype "passive"))
    )
    (net (code "9") (name "/EN_Y") (class "Default")
      (node (ref "R11") (pin "1") (pinfunction "1_1") (pintype "passive"))
      (node (ref "U2") (pin "2") (pinfunction "ENABLE_2") (pintype "open_collector"))
      (node (ref "U5") (pin "61") (pinfunction "PB8/TIM4_CH3/SDIO_D4_61") (pintype "passive"))
    )
    (net (code "10") (name "/EN_Z") (class "Default")
      (node (ref "R13") (pin "1") (pinfunction "1_1") (pintype "passive"))
      (node (ref "U3") (pin "2") (pinfunction "ENABLE_2") (pintype "open_collector"))
      (node (ref "U5") (pin "57") (pinfunction "PB5/I2C1_SMBAI/SPI3_MOSI/I2S3_SD_57") (pintype "passive"))
    )
    (net (code "11") (name "/HEATER1") (class "Default")
      (node (ref "R46") (pin "1") (pinfunction "1_1") (pintype "passive"))
      (node (ref "U5") (pin "15") (pinfunction "PA1/USART2_RTS/ADC123_IN1/TIM5_CH2/TIM2_CH2_15") (pintype "passive"))
    )
    (net (code "12") (name "/IR") (class "Default")
      (node (ref "R60") (pin "2") (pinfunction "2_2") (pintype "passive"))
      (node (ref "U5") (pin "41") (pinfunction "PA8/USART1_CK/TIM1_CH1/MCO_41") (pintype "passive"))
    )
    (net (code "13") (name "/KEY0") (class "Default")
      (node (ref "P4") (pin "3") (pinfunction "3_3") (pintype "passive"))
      (node (ref "R48") (pin "1") (pinfunction "1_1") (pintype "passive"))
      (node (ref "U5") (pin "35") (pinfunction "PB14/SPI2_MISO/USART3_RTS/TIM1_CH2N_35") (pintype "passive"))
    )
    (net (code "14") (name "/KEY1") (class "Default")
      (node (ref "P4") (pin "2") (pinfunction "2_2") (pintype "passive"))
      (node (ref "R49") (pin "1") (pinfunction "1_1") (pintype "passive"))
      (node (ref "U5") (pin "34") (pinfunction "PB13/SPI2_SCK/I2S2_CK/USART3_CTS/TIM1_CH1N_34") (pintype "passive"))
    )
    (net (code "15") (name "/KEY2") (class "Default")
      (node (ref "P4") (pin "1") (pinfunction "1_1") (pintype "passive"))
      (node (ref "R50") (pin "1") (pinfunction "1_1") (pintype "passive"))
      (node (ref "U5") (pin "33") (pinfunction "PB12/SPI2_NSS/I2S2_WS/I2C2_SMBAI/USART3_CK/TIM1BKIN_33") (pintype "passive"))
    )
    (net (code "16") (name "/NRST") (class "Default")
      (node (ref "C43") (pin "1") (pinfunction "1_1") (pintype "passive"))
      (node (ref "C50") (pin "1") (pinfunction "1_1") (pintype "passive"))
      (node (ref "P3") (pin "1") (pinfunction "1_1") (pintype "passive"))
      (node (ref "R32") (pin "1") (pinfunction "1_1") (pintype "passive"))
      (node (ref "U5") (pin "7") (pinfunction "NRST_7") (pintype "passive"))
    )
    (net (code "17") (name "/P3.2") (class "Default")
      (node (ref "U5") (pin "9") (pinfunction "PC1/ADC123_IN11_9") (pintype "passive"))
      (node (ref "U9") (pin "7") (pinfunction "P3.2/INT0_7") (pintype "passive"))
    )
    (net (code "18") (name "/P3.3") (class "Default")
      (node (ref "R58") (pin "2") (pinfunction "2_2") (pintype "passive"))
      (node (ref "U9") (pin "8") (pinfunction "P3.3/INT1/RSTOUT_LOW_8") (pintype "passive"))
    )
    (net (code "19") (name "/PC2") (class "Default")
      (node (ref "U5") (pin "10") (pinfunction "PC2/ADC123_IN12_10") (pintype "passive"))
      (node (ref "XH2") (pin "1") (pinfunction "1_1") (pintype "passive"))
    )
    (net (code "20") (name "/PC3") (class "Default")
      (node (ref "U5") (pin "11") (pinfunction "PC3/ADC123_IN13_11") (pintype "passive"))
      (node (ref "XH3") (pin "1") (pinfunction "1_1") (pintype "passive"))
    )
    (net (code "21") (name "/RXD") (class "Default")
      (node (ref "U5") (pin "42") (pinfunction "PA9/USART1_TX/TIM1_CH2_42") (pintype "passive"))
      (node (ref "U7") (pin "3") (pinfunction "RXD_3") (pintype "open_collector"))
    )
    (net (code "22") (name "/SCL") (class "Default")
      (node (ref "P5") (pin "2") (pinfunction "2_2") (pintype "passive"))
      (node (ref "R51") (pin "1") (pinfunction "1_1") (pintype "passive"))
      (node (ref "U5") (pin "29") (pinfunction "PB10/I2C2_SCL/USART3_TX_29") (pintype "passive"))
    )
    (net (code "23") (name "/SDA") (class "Default")
      (node (ref "P5") (pin "1") (pinfunction "1_1") (pintype "passive"))
      (node (ref "R52") (pin "1") (pinfunction "1_1") (pintype "passive"))
      (node (ref "U5") (pin "30") (pinfunction "PB11/I2C2_SDA/USART3_RX_30") (pintype "passive"))
    )
    (net (code "24") (name "/SD_CLK") (class "Default")
      (node (ref "TF1") (pin "5") (pinfunction "CLK_5") (pintype "passive"))
      (node (ref "U5") (pin "53") (pinfunction "PC12/UART5_TX/SDIO_CK_53") (pintype "passive"))
    )
    (net (code "25") (name "/SD_CMD") (class "Default")
      (node (ref "R36") (pin "2") (pinfunction "2_2") (pintype "passive"))
      (node (ref "TF1") (pin "3") (pinfunction "CMD_3") (pintype "passive"))
      (node (ref "U5") (pin "54") (pinfunction "PD2/TIM3_ETR/UART5_RX/SDIO_CMD_54") (pintype "passive"))
    )
    (net (code "26") (name "/SD_D0") (class "Default")
      (node (ref "R40") (pin "2") (pinfunction "2_2") (pintype "passive"))
      (node (ref "TF1") (pin "7") (pinfunction "DAT0_7") (pintype "passive"))
      (node (ref "U5") (pin "39") (pinfunction "PC8/TIM8_CH3/SDIO_D0_39") (pintype "passive"))
    )
    (net (code "27") (name "/SD_D1") (class "Default")
      (node (ref "R39") (pin "2") (pinfunction "2_2") (pintype "passive"))
      (node (ref "TF1") (pin "8") (pinfunction "DAT1_8") (pintype "passive"))
      (node (ref "U5") (pin "40") (pinfunction "PC9/TIM8_CH4/SDIO_D1_40") (pintype "passive"))
    )
    (net (code "28") (name "/SD_D2") (class "Default")
      (node (ref "R38") (pin "2") (pinfunction "2_2") (pintype "passive"))
      (node (ref "TF1") (pin "1") (pinfunction "DAT2_1") (pintype "passive"))
      (node (ref "U5") (pin "51") (pinfunction "PC10/UART4_TX/SDIO_D2_51") (pintype "passive"))
    )
    (net (code "29") (name "/SD_D3") (class "Default")
      (node (ref "R37") (pin "2") (pinfunction "2_2") (pintype "passive"))
      (node (ref "TF1") (pin "2") (pinfunction "CD/DAT3_2") (pintype "passive"))
      (node (ref "U5") (pin "52") (pinfunction "PC11/UART4_RX/SDIO_D3_52") (pintype "passive"))
    )
    (net (code "30") (name "/SD_DETECT") (class "Default")
      (node (ref "R35") (pin "2") (pinfunction "2_2") (pintype "passive"))
      (node (ref "TF1") (pin "9") (pinfunction "Detect_9") (pintype "passive"))
      (node (ref "U5") (pin "38") (pinfunction "PC7/I2S3_MCK/TIM8_CH2/SDIO_D7_38") (pintype "passive"))
    )
    (net (code "31") (name "/STEP_E1") (class "Default")
      (node (ref "U4") (pin "16") (pinfunction "STEP_16") (pintype "open_collector"))
      (node (ref "U5") (pin "37") (pinfunction "PC6/I2S2_MCK/TIM8_CH1/SDIO_D6_37") (pintype "passive"))
    )
    (net (code "32") (name "/STEP_X") (class "Default")
      (node (ref "U1") (pin "16") (pinfunction "STEP_16") (pintype "open_collector"))
      (node (ref "U5") (pin "27") (pinfunction "PB1/ADC12_IN9/TIM3_CH4/TIM8_CH3N_27") (pintype "passive"))
    )
    (net (code "33") (name "/STEP_Y") (class "Default")
      (node (ref "U2") (pin "16") (pinfunction "STEP_16") (pintype "open_collector"))
      (node (ref "U5") (pin "59") (pinfunction "PB7/I2C1_SDA/FSMC_NADV/TIM4_CH2_59") (pintype "passive"))
    )
    (net (code "34") (name "/STEP_Z") (class "Default")
      (node (ref "U3") (pin "16") (pinfunction "STEP_16") (pintype "open_collector"))
      (node (ref "U5") (pin "56") (pinfunction "PB4/JNTRST/SPI3_MISO_56") (pintype "passive"))
    )
    (net (code "35") (name "/SWCLK") (class "Default")
      (node (ref "P1") (pin "3") (pinfunction "3_3") (pintype "passive"))
      (node (ref "U5") (pin "49") (pinfunction "PA14/JTCK/SWCLK_49") (pintype "passive"))
    )
    (net (code "36") (name "/SWDIO") (class "Default")
      (node (ref "P1") (pin "2") (pinfunction "2_2") (pintype "passive"))
      (node (ref "U5") (pin "46") (pinfunction "PA13/JTMS/SWDIO_46") (pintype "passive"))
    )
    (net (code "37") (name "/TH1") (class "Default")
      (node (ref "C49") (pin "2") (pinfunction "2_2") (pintype "passive"))
      (node (ref "R44") (pin "2") (pinfunction "2_2") (pintype "passive"))
      (node (ref "TH") (pin "1") (pinfunction "1_1") (pintype "passive"))
      (node (ref "U5") (pin "8") (pinfunction "PC0/ADC123_IN10_8") (pintype "passive"))
    )
    (net (code "38") (name "/TXD") (class "Default")
      (node (ref "D6") (pin "2") (pinfunction "K_2") (pintype "passive"))
      (node (ref "U5") (pin "43") (pinfunction "PA10/USART1_RX/TIM1_CH3_43") (pintype "passive"))
      (node (ref "U7") (pin "2") (pinfunction "TXD_2") (pintype "open_collector"))
    )
    (net (code "39") (name "/WS2812") (class "Default")
      (node (ref "U5") (pin "62") (pinfunction "PB9/TIM4_CH4/SDIO_D5_62") (pintype "passive"))
      (node (ref "XH1") (pin "1") (pinfunction "1_1") (pintype "passive"))
    )
    (net (code "40") (name "/X-") (class "Default")
      (node (ref "C46") (pin "2") (pinfunction "2_2") (pintype "passive"))
      (node (ref "R41") (pin "1") (pinfunction "1_1") (pintype "passive"))
      (node (ref "U5") (pin "21") (pinfunction "PA5/SPI1_SCK/DAC_OUT2/ADC12_IN5_21") (pintype "passive"))
      (node (ref "X-") (pin "1") (pinfunction "1_1") (pintype "passive"))
    )
    (net (code "41") (name "/Y-") (class "Default")
      (node (ref "C47") (pin "2") (pinfunction "2_2") (pintype "passive"))
      (node (ref "R42") (pin "1") (pinfunction "1_1") (pintype "passive"))
      (node (ref "U5") (pin "22") (pinfunction "PA6/SPI1_MISO/TIM8_BKIN/ADC12_IN6/TIM3_CH1_22") (pintype "passive"))
      (node (ref "Y-") (pin "1") (pinfunction "1_1") (pintype "passive"))
    )
    (net (code "42") (name "/Z-") (class "Default")
      (node (ref "C48") (pin "2") (pinfunction "2_2") (pintype "passive"))
      (node (ref "R43") (pin "1") (pinfunction "1_1") (pintype "passive"))
      (node (ref "U5") (pin "23") (pinfunction "PA7/SPI1_MOSI/TIM8_CH1N/ADC12_IN7/TIM3_CH2_23") (pintype "passive"))
      (node (ref "Z-") (pin "1") (pinfunction "1_1") (pintype "passive"))
    )
    (net (code "43") (name "3V3") (class "Default")
      (node (ref "B1") (pin "1") (pinfunction "1_1") (pintype "passive"))
      (node (ref "C26") (pin "1") (pinfunction "1_1") (pintype "passive"))
      (node (ref "C28") (pin "1") (pinfunction "1_1") (pintype "passive"))
      (node (ref "C37") (pin "1") (pinfunction "1_1") (pintype "passive"))
      (node (ref "C38") (pin "1") (pinfunction "1_1") (pintype "passive"))
      (node (ref "C39") (pin "1") (pinfunction "1_1") (pintype "passive"))
      (node (ref "C40") (pin "1") (pinfunction "1_1") (pintype "passive"))
      (node (ref "C41") (pin "1") (pinfunction "1_1") (pintype "passive"))
      (node (ref "C51") (pin "2") (pinfunction "2_2") (pintype "passive"))
      (node (ref "L2") (pin "2") (pinfunction "2_2") (pintype "passive"))
      (node (ref "P1") (pin "1") (pinfunction "1_1") (pintype "passive"))
      (node (ref "P5") (pin "4") (pinfunction "4_4") (pintype "passive"))
      (node (ref "R1") (pin "2") (pinfunction "2_2") (pintype "passive"))
      (node (ref "R11") (pin "2") (pinfunction "2_2") (pintype "passive"))
      (node (ref "R13") (pin "2") (pinfunction "2_2") (pintype "passive"))
      (node (ref "R15") (pin "2") (pinfunction "2_2") (pintype "passive"))
      (node (ref "R17") (pin "1") (pinfunction "1_1") (pintype "passive"))
      (node (ref "R19") (pin "1") (pinfunction "1_1") (pintype "passive"))
      (node (ref "R2") (pin "2") (pinfunction "2_2") (pintype "passive"))
      (node (ref "R21") (pin "1") (pinfunction "1_1") (pintype "passive"))
      (node (ref "R23") (pin "1") (pinfunction "1_1") (pintype "passive"))
      (node (ref "R25") (pin "2") (pinfunction "2_2") (pintype "passive"))
      (node (ref "R27") (pin "2") (pinfunction "2_2") (pintype "passive"))
      (node (ref "R3") (pin "2") (pinfunction "2_2") (pintype "passive"))
      (node (ref "R32") (pin "2") (pinfunction "2_2") (pintype "passive"))
      (node (ref "R33") (pin "2") (pinfunction "2_2") (pintype "passive"))
      (node (ref "R35") (pin "1") (pinfunction "1_1") (pintype "passive"))
      (node (ref "R36") (pin "1") (pinfunction "1_1") (pintype "passive"))
      (node (ref "R37") (pin "1") (pinfunction "1_1") (pintype "passive"))
      (node (ref "R38") (pin "1") (pinfunction "1_1") (pintype "passive"))
      (node (ref "R39") (pin "1") (pinfunction "1_1") (pintype "passive"))
      (node (ref "R4") (pin "2") (pinfunction "2_2") (pintype "passive"))
      (node (ref "R40") (pin "1") (pinfunction "1_1") (pintype "passive"))
      (node (ref "R41") (pin "2") (pinfunction "2_2") (pintype "passive"))
      (node (ref "R42") (pin "2") (pinfunction "2_2") (pintype "passive"))
      (node (ref "R43") (pin "2") (pinfunction "2_2") (pintype "passive"))
      (node (ref "R44") (pin "1") (pinfunction "1_1") (pintype "passive"))
      (node (ref "R48") (pin "2") (pinfunction "2_2") (pintype "passive"))
      (node (ref "R49") (pin "2") (pinfunction "2_2") (pintype "passive"))
      (node (ref "R50") (pin "2") (pinfunction "2_2") (pintype "passive"))
      (node (ref "R51") (pin "2") (pinfunction "2_2") (pintype "passive"))
      (node (ref "R52") (pin "2") (pinfunction "2_2") (pintype "passive"))
      (node (ref "R53") (pin "1") (pinfunction "1_1") (pintype "passive"))
      (node (ref "R9") (pin "2") (pinfunction "2_2") (pintype "passive"))
      (node (ref "TF1") (pin "4") (pinfunction "VCC_4") (pintype "passive"))
      (node (ref "U1") (pin "10") (pinfunction "MS2_10") (pintype "open_collector"))
      (node (ref "U1") (pin "11") (pinfunction "MS3_11") (pintype "open_collector"))
      (node (ref "U1") (pin "15") (pinfunction "VCC_15") (pintype "open_collector"))
      (node (ref "U1") (pin "9") (pinfunction "MS1_9") (pintype "open_collector"))
      (node (ref "U2") (pin "10") (pinfunction "MS2_10") (pintype "open_collector"))
      (node (ref "U2") (pin "11") (pinfunction "MS3_11") (pintype "open_collector"))
      (node (ref "U2") (pin "15") (pinfunction "VCC_15") (pintype "open_collector"))
      (node (ref "U2") (pin "9") (pinfunction "MS1_9") (pintype "open_collector"))
      (node (ref "U3") (pin "10") (pinfunction "MS2_10") (pintype "open_collector"))
      (node (ref "U3") (pin "11") (pinfunction "MS3_11") (pintype "open_collector"))
      (node (ref "U3") (pin "15") (pinfunction "VCC_15") (pintype "open_collector"))
      (node (ref "U3") (pin "9") (pinfunction "MS1_9") (pintype "open_collector"))
      (node (ref "U4") (pin "10") (pinfunction "MS2_10") (pintype "open_collector"))
      (node (ref "U4") (pin "11") (pinfunction "MS3_11") (pintype "open_collector"))
      (node (ref "U4") (pin "15") (pinfunction "VCC_15") (pintype "open_collector"))
      (node (ref "U4") (pin "9") (pinfunction "MS1_9") (pintype "open_collector"))
      (node (ref "U5") (pin "19") (pinfunction "VDD_4_19") (pintype "passive"))
      (node (ref "U5") (pin "32") (pinfunction "VDD_1_32") (pintype "passive"))
      (node (ref "U5") (pin "48") (pinfunction "VDD_2_48") (pintype "passive"))
      (node (ref "U5") (pin "64") (pinfunction "VDD_3_64") (pintype "passive"))
      (node (ref "U7") (pin "16") (pinfunction "VCC_16") (pintype "open_collector"))
      (node (ref "U7") (pin "4") (pinfunction "3V3_4") (pintype "open_collector"))
    )
    (net (code "44") (name "5V") (class "Default")
      (node (ref "C42") (pin "2") (pinfunction "2_2") (pintype "passive"))
      (node (ref "C44") (pin "2") (pinfunction "2_2") (pintype "passive"))
      (node (ref "C52") (pin "2") (pinfunction "2_2") (pintype "passive"))
      (node (ref "D7") (pin "2") (pinfunction "K_2") (pintype "passive"))
      (node (ref "JK1") (pin "2") (pinfunction "2_2") (pintype "passive"))
      (node (ref "L3") (pin "2") (pinfunction "2_2") (pintype "passive"))
      (node (ref "R54") (pin "2") (pinfunction "2_2") (pintype "passive"))
      (node (ref "R55") (pin "2") (pinfunction "2_2") (pintype "passive"))
      (node (ref "R56") (pin "2") (pinfunction "2_2") (pintype "passive"))
      (node (ref "U9") (pin "2") (pinfunction "VCC_2") (pintype "passive"))
      (node (ref "XH1") (pin "3") (pinfunction "3_3") (pintype "passive"))
      (node (ref "XH2") (pin "3") (pinfunction "3_3") (pintype "passive"))
      (node (ref "XH3") (pin "3") (pinfunction "3_3") (pintype "passive"))
    )
    (net (code "45") (name "12V") (class "Default")
      (node (ref "1") (pin "1") (pinfunction "1_1") (pintype "passive"))
      (node (ref "C45") (pin "2") (pinfunction "2_2") (pintype "passive"))
      (node (ref "JK1") (pin "3") (pinfunction "3_3") (pintype "passive"))
      (node (ref "U8") (pin "7") (pinfunction "VIN_7") (pintype "passive"))
    )
    (net (code "46") (name "12V_VIN") (class "Default")
      (node (ref "F1") (pin "1") (pinfunction "1_1") (pintype "passive"))
      (node (ref "JK1") (pin "4") (pinfunction "4_4") (pintype "passive"))
    )
    (net (code "47") (name "GND") (class "Default")
      (node (ref "1") (pin "2") (pinfunction "2_2") (pintype "passive"))
      (node (ref "C10") (pin "2") (pinfunction "2_2") (pintype "passive"))
      (node (ref "C11") (pin "2") (pinfunction "2_2") (pintype "passive"))
      (node (ref "C12") (pin "2") (pinfunction "2_2") (pintype "passive"))
      (node (ref "C13") (pin "2") (pinfunction "2_2") (pintype "passive"))
      (node (ref "C14") (pin "2") (pinfunction "2_2") (pintype "passive"))
      (node (ref "C15") (pin "2") (pinfunction "2_2") (pintype "passive"))
      (node (ref "C16") (pin "2") (pinfunction "2_2") (pintype "passive"))
      (node (ref "C21") (pin "2") (pinfunction "2_2") (pintype "passive"))
      (node (ref "C22") (pin "2") (pinfunction "2_2") (pintype "passive"))
      (node (ref "C23") (pin "2") (pinfunction "2_2") (pintype "passive"))
      (node (ref "C24") (pin "2") (pinfunction "2_2") (pintype "passive"))
      (node (ref "C26") (pin "2") (pinfunction "2_2") (pintype "passive"))
      (node (ref "C27") (pin "2") (pinfunction "2_2") (pintype "passive"))
      (node (ref "C28") (pin "2") (pinfunction "2_2") (pintype "passive"))
      (node (ref "C30") (pin "2") (pinfunction "2_2") (pintype "passive"))
      (node (ref "C31") (pin "2") (pinfunction "2_2") (pintype "passive"))
      (node (ref "C33") (pin "1") (pinfunction "1_1") (pintype "passive"))
      (node (ref "C34") (pin "1") (pinfunction "1_1") (pintype "passive"))
      (node (ref "C35") (pin "2") (pinfunction "2_2") (pintype "passive"))
      (node (ref "C36") (pin "2") (pinfunction "2_2") (pintype "passive"))
      (node (ref "C37") (pin "2") (pinfunction "2_2") (pintype "passive"))
      (node (ref "C38") (pin "2") (pinfunction "2_2") (pintype "passive"))
      (node (ref "C39") (pin "2") (pinfunction "2_2") (pintype "passive"))
      (node (ref "C40") (pin "2") (pinfunction "2_2") (pintype "passive"))
      (node (ref "C41") (pin "2") (pinfunction "2_2") (pintype "passive"))
      (node (ref "C42") (pin "1") (pinfunction "1_1") (pintype "passive"))
      (node (ref "C44") (pin "1") (pinfunction "1_1") (pintype "passive"))
      (node (ref "C45") (pin "1") (pinfunction "1_1") (pintype "passive"))
      (node (ref "C46") (pin "1") (pinfunction "1_1") (pintype "passive"))
      (node (ref "C47") (pin "1") (pinfunction "1_1") (pintype "passive"))
      (node (ref "C48") (pin "1") (pinfunction "1_1") (pintype "passive"))
      (node (ref "C49") (pin "1") (pinfunction "1_1") (pintype "passive"))
      (node (ref "C5") (pin "2") (pinfunction "2_2") (pintype "passive"))
      (node (ref "C50") (pin "2") (pinfunction "2_2") (pintype "passive"))
      (node (ref "C51") (pin "1") (pinfunction "1_1") (pintype "passive"))
      (node (ref "C52") (pin "1") (pinfunction "1_1") (pintype "passive"))
      (node (ref "C6") (pin "2") (pinfunction "2_2") (pintype "passive"))
      (node (ref "C7") (pin "2") (pinfunction "2_2") (pintype "passive"))
      (node (ref "C8") (pin "2") (pinfunction "2_2") (pintype "passive"))
      (node (ref "C9") (pin "2") (pinfunction "2_2") (pintype "passive"))
      (node (ref "D1") (pin "2") (pinfunction "K_2") (pintype "passive"))
      (node (ref "D2") (pin "1") (pinfunction "A_1") (pintype "passive"))
      (node (ref "D5") (pin "1") (pinfunction "A_1") (pintype "passive"))
      (node (ref "D8") (pin "A") (pinfunction "A_A") (pintype "passive"))
      (node (ref "FAN1") (pin "2") (pinfunction "2_2") (pintype "passive"))
      (node (ref "FAN2") (pin "2") (pinfunction "2_2") (pintype "passive"))
      (node (ref "P1") (pin "4") (pinfunction "4_4") (pintype "passive"))
      (node (ref "P3") (pin "2") (pinfunction "2_2") (pintype "passive"))
      (node (ref "P4") (pin "4") (pinfunction "4_4") (pintype "passive"))
      (node (ref "P5") (pin "3") (pinfunction "3_3") (pintype "passive"))
      (node (ref "Q1") (pin "2") (pinfunction "G_2") (pintype "passive"))
      (node (ref "Q2") (pin "2") (pinfunction "E_2") (pintype "passive"))
      (node (ref "Q3") (pin "E") (pinfunction "E_E") (pintype "passive"))
      (node (ref "R10") (pin "2") (pinfunction "2_2") (pintype "passive"))
      (node (ref "R12") (pin "2") (pinfunction "2_2") (pintype "passive"))
      (node (ref "R14") (pin "2") (pinfunction "2_2") (pintype "passive"))
      (node (ref "R16") (pin "2") (pinfunction "2_2") (pintype "passive"))
      (node (ref "R18") (pin "2") (pinfunction "2_2") (pintype "passive"))
      (node (ref "R20") (pin "2") (pinfunction "2_2") (pintype "passive"))
      (node (ref "R22") (pin "2") (pinfunction "2_2") (pintype "passive"))
      (node (ref "R24") (pin "2") (pinfunction "2_2") (pintype "passive"))
      (node (ref "R28") (pin "1") (pinfunction "1_1") (pintype "passive"))
      (node (ref "R29") (pin "1") (pinfunction "1_1") (pintype "passive"))
      (node (ref "R30") (pin "2") (pinfunction "2_2") (pintype "passive"))
      (node (ref "R31") (pin "2") (pinfunction "2_2") (pintype "passive"))
      (node (ref "R34") (pin "1") (pinfunction "1_1") (pintype "passive"))
      (node (ref "R47") (pin "2") (pinfunction "2_2") (pintype "passive"))
      (node (ref "R5") (pin "2") (pinfunction "2_2") (pintype "passive"))
      (node (ref "R57") (pin "1") (pinfunction "1_1") (pintype "passive"))
      (node (ref "R59") (pin "1") (pinfunction "1_1") (pintype "passive"))
      (node (ref "R6") (pin "2") (pinfunction "2_2") (pintype "passive"))
      (node (ref "R7") (pin "2") (pinfunction "2_2") (pintype "passive"))
      (node (ref "R8") (pin "2") (pinfunction "2_2") (pintype "passive"))
      (node (ref "RP1") (pin "2") (pintype "passive"))
      (node (ref "RP2") (pin "2") (pintype "passive"))
      (node (ref "RP3") (pin "2") (pintype "passive"))
      (node (ref "RP4") (pin "2") (pintype "passive"))
      (node (ref "TF1") (pin "0") (pinfunction "GND_0") (pintype "passive"))
      (node (ref "TF1") (pin "6") (pinfunction "GND_6") (pintype "passive"))
      (node (ref "TH") (pin "2") (pinfunction "2_2") (pintype "passive"))
      (node (ref "TH1") (pin "2") (pinfunction "2_2") (pintype "passive"))
      (node (ref "U1") (pin "18") (pinfunction "GND_18") (pintype "open_collector"))
      (node (ref "U1") (pin "20") (pinfunction "NC_20") (pintype "open_collector"))
      (node (ref "U1") (pin "25") (pinfunction "NC_25") (pintype "open_collector"))
      (node (ref "U1") (pin "29") (pinfunction "GND_29") (pintype "open_collector"))
      (node (ref "U1") (pin "3") (pinfunction "GND_3") (pintype "open_collector"))
      (node (ref "U1") (pin "7") (pinfunction "NC_7") (pintype "open_collector"))
      (node (ref "U2") (pin "18") (pinfunction "GND_18") (pintype "open_collector"))
      (node (ref "U2") (pin "20") (pinfunction "NC_20") (pintype "open_collector"))
      (node (ref "U2") (pin "25") (pinfunction "NC_25") (pintype "open_collector"))
      (node (ref "U2") (pin "29") (pinfunction "GND_29") (pintype "open_collector"))
      (node (ref "U2") (pin "3") (pinfunction "GND_3") (pintype "open_collector"))
      (node (ref "U2") (pin "7") (pinfunction "NC_7") (pintype "open_collector"))
      (node (ref "U3") (pin "18") (pinfunction "GND_18") (pintype "open_collector"))
      (node (ref "U3") (pin "20") (pinfunction "NC_20") (pintype "open_collector"))
      (node (ref "U3") (pin "25") (pinfunction "NC_25") (pintype "open_collector"))
      (node (ref "U3") (pin "29") (pinfunction "GND_29") (pintype "open_collector"))
      (node (ref "U3") (pin "3") (pinfunction "GND_3") (pintype "open_collector"))
      (node (ref "U3") (pin "7") (pinfunction "NC_7") (pintype "open_collector"))
      (node (ref "U4") (pin "18") (pinfunction "GND_18") (pintype "open_collector"))
      (node (ref "U4") (pin "20") (pinfunction "NC_20") (pintype "open_collector"))
      (node (ref "U4") (pin "25") (pinfunction "NC_25") (pintype "open_collector"))
      (node (ref "U4") (pin "29") (pinfunction "GND_29") (pintype "open_collector"))
      (node (ref "U4") (pin "3") (pinfunction "GND_3") (pintype "open_collector"))
      (node (ref "U4") (pin "7") (pinfunction "NC_7") (pintype "open_collector"))
      (node (ref "U5") (pin "18") (pinfunction "VSS_4_18") (pintype "passive"))
      (node (ref "U5") (pin "31") (pinfunction "VSS_1_31") (pintype "passive"))
      (node (ref "U5") (pin "47") (pinfunction "VSS_2_47") (pintype "passive"))
      (node (ref "U5") (pin "63") (pinfunction "VSS_3_63") (pintype "passive"))
      (node (ref "U6") (pin "5") (pinfunction "GND_5") (pintype "passive"))
      (node (ref "U7") (pin "1") (pinfunction "GND_1") (pintype "open_collector"))
      (node (ref "U8") (pin "6") (pinfunction "GND_6") (pintype "passive"))
      (node (ref "U9") (pin "4") (pinfunction "GND_4") (pintype "passive"))
      (node (ref "USB1") (pin "1") (pinfunction "1_1") (pintype "passive"))
      (node (ref "X-") (pin "2") (pinfunction "2_2") (pintype "passive"))
      (node (ref "XH1") (pin "2") (pinfunction "2_2") (pintype "passive"))
      (node (ref "XH2") (pin "2") (pinfunction "2_2") (pintype "passive"))
      (node (ref "XH3") (pin "2") (pinfunction "2_2") (pintype "passive"))
      (node (ref "Y-") (pin "2") (pinfunction "2_2") (pintype "passive"))
      (node (ref "Y3") (pin "2") (pinfunction "2_2") (pintype "passive"))
      (node (ref "Z-") (pin "2") (pinfunction "2_2") (pintype "passive"))
    )
    (net (code "48") (name "Net-(B1-Pad2)") (class "Default")
      (node (ref "B1") (pin "2") (pinfunction "2_2") (pintype "passive"))
      (node (ref "Q3") (pin "C") (pinfunction "C_C") (pintype "passive"))
    )
    (net (code "49") (name "Net-(C27-Pad1)") (class "Default")
      (node (ref "C27") (pin "1") (pinfunction "1_1") (pintype "passive"))
      (node (ref "L1") (pin "2") (pinfunction "2_2") (pintype "passive"))
      (node (ref "L2") (pin "1") (pinfunction "1_1") (pintype "passive"))
    )
    (net (code "50") (name "Net-(C32-Pad2)") (class "Default")
      (node (ref "C32") (pin "2") (pinfunction "2_2") (pintype "passive"))
      (node (ref "R30") (pin "1") (pinfunction "1_1") (pintype "passive"))
    )
    (net (code "51") (name "Net-(D1-A)") (class "Default")
      (node (ref "D1") (pin "1") (pinfunction "A_1") (pintype "passive"))
      (node (ref "R25") (pin "1") (pinfunction "1_1") (pintype "passive"))
    )
    (net (code "52") (name "Net-(D3-A)") (class "Default")
      (node (ref "D3") (pin "1") (pinfunction "A_1") (pintype "passive"))
      (node (ref "USB1") (pin "5") (pinfunction "5_5") (pintype "passive"))
    )
    (net (code "53") (name "Net-(D4-A)") (class "Default")
      (node (ref "D4") (pin "1") (pinfunction "A_1") (pintype "passive"))
      (node (ref "R45") (pin "2") (pinfunction "2_2") (pintype "passive"))
    )
    (net (code "54") (name "Net-(D4-K)") (class "Default")
      (node (ref "D4") (pin "2") (pinfunction "K_2") (pintype "passive"))
      (node (ref "HEATER1") (pin "2") (pinfunction "2_2") (pintype "passive"))
      (node (ref "Q1") (pin "3") (pinfunction "S_3") (pintype "passive"))
    )
    (net (code "55") (name "Net-(D5-K)") (class "Default")
      (node (ref "C25") (pin "1") (pinfunction "1_1") (pintype "passive"))
      (node (ref "D5") (pin "2") (pinfunction "K_2") (pintype "passive"))
      (node (ref "L1") (pin "1") (pinfunction "1_1") (pintype "passive"))
      (node (ref "U6") (pin "1") (pinfunction "SW_1") (pintype "passive"))
    )
    (net (code "56") (name "Net-(D6-A)") (class "Default")
      (node (ref "D6") (pin "1") (pinfunction "A_1") (pintype "passive"))
      (node (ref "R53") (pin "2") (pinfunction "2_2") (pintype "passive"))
    )
    (net (code "57") (name "Net-(D7-A)") (class "Default")
      (node (ref "D7") (pin "1") (pinfunction "A_1") (pintype "passive"))
      (node (ref "JK1") (pin "1") (pinfunction "1_1") (pintype "passive"))
      (node (ref "Q2") (pin "3") (pinfunction "C_3") (pintype "passive"))
    )
    (net (code "58") (name "Net-(Q1-D)") (class "Default")
      (node (ref "Q1") (pin "1") (pinfunction "D_1") (pintype "passive"))
      (node (ref "R46") (pin "2") (pinfunction "2_2") (pintype "passive"))
      (node (ref "R47") (pin "1") (pinfunction "1_1") (pintype "passive"))
    )
    (net (code "59") (name "Net-(Q2-B)") (class "Default")
      (node (ref "Q2") (pin "1") (pinfunction "B_1") (pintype "passive"))
      (node (ref "R58") (pin "1") (pinfunction "1_1") (pintype "passive"))
      (node (ref "R59") (pin "2") (pinfunction "2_2") (pintype "passive"))
    )
    (net (code "60") (name "Net-(Q3-PadB)") (class "Default")
      (node (ref "Q3") (pin "B") (pinfunction "B_B") (pintype "passive"))
      (node (ref "R60") (pin "1") (pinfunction "1_1") (pintype "passive"))
    )
    (net (code "61") (name "Net-(R17-Pad2)") (class "Default")
      (node (ref "R17") (pin "2") (pinfunction "2_2") (pintype "passive"))
      (node (ref "RP1") (pin "3") (pintype "passive"))
    )
    (net (code "62") (name "Net-(R19-Pad2)") (class "Default")
      (node (ref "R19") (pin "2") (pinfunction "2_2") (pintype "passive"))
      (node (ref "RP2") (pin "3") (pintype "passive"))
    )
    (net (code "63") (name "Net-(R21-Pad2)") (class "Default")
      (node (ref "R21") (pin "2") (pinfunction "2_2") (pintype "passive"))
      (node (ref "RP3") (pin "3") (pintype "passive"))
    )
    (net (code "64") (name "Net-(R23-Pad2)") (class "Default")
      (node (ref "R23") (pin "2") (pinfunction "2_2") (pintype "passive"))
      (node (ref "RP4") (pin "3") (pintype "passive"))
    )
    (net (code "65") (name "Net-(U1-CP1)") (class "Default")
      (node (ref "C1") (pin "1") (pinfunction "1_1") (pintype "passive"))
      (node (ref "U1") (pin "4") (pinfunction "CP1_4") (pintype "open_collector"))
    )
    (net (code "66") (name "Net-(U1-CP2)") (class "Default")
      (node (ref "C1") (pin "2") (pinfunction "2_2") (pintype "passive"))
      (node (ref "U1") (pin "5") (pinfunction "CP2_5") (pintype "open_collector"))
    )
    (net (code "67") (name "Net-(U1-OUT1A)") (class "Default")
      (node (ref "U1") (pin "24") (pinfunction "OUT1A_24") (pintype "open_collector"))
      (node (ref "X") (pin "2") (pinfunction "2_2") (pintype "passive"))
    )
    (net (code "68") (name "Net-(U1-OUT1B)") (class "Default")
      (node (ref "U1") (pin "21") (pinfunction "OUT1B_21") (pintype "open_collector"))
      (node (ref "X") (pin "1") (pinfunction "1_1") (pintype "passive"))
    )
    (net (code "69") (name "Net-(U1-OUT2A)") (class "Default")
      (node (ref "U1") (pin "26") (pinfunction "OUT2A_26") (pintype "open_collector"))
      (node (ref "X") (pin "3") (pinfunction "3_3") (pintype "passive"))
    )
    (net (code "70") (name "Net-(U1-OUT2B)") (class "Default")
      (node (ref "U1") (pin "1") (pinfunction "OUT2B_1") (pintype "open_collector"))
      (node (ref "X") (pin "4") (pinfunction "4_4") (pintype "passive"))
    )
    (net (code "71") (name "Net-(U1-REF)") (class "Default")
      (node (ref "RP1") (pin "1") (pintype "passive"))
      (node (ref "U1") (pin "17") (pinfunction "REF_17") (pintype "open_collector"))
    )
    (net (code "72") (name "Net-(U1-RESET)") (class "Default")
      (node (ref "R1") (pin "1") (pinfunction "1_1") (pintype "passive"))
      (node (ref "U1") (pin "12") (pinfunction "RESET_12") (pintype "open_collector"))
      (node (ref "U1") (pin "14") (pinfunction "SLEEP_14") (pintype "open_collector"))
    )
    (net (code "73") (name "Net-(U1-ROSC)") (class "Default")
      (node (ref "R5") (pin "1") (pinfunction "1_1") (pintype "passive"))
      (node (ref "U1") (pin "13") (pinfunction "ROSC_13") (pintype "open_collector"))
    )
    (net (code "74") (name "Net-(U1-SENSE1)") (class "Default")
      (node (ref "R10") (pin "1") (pinfunction "1_1") (pintype "passive"))
      (node (ref "U1") (pin "23") (pinfunction "SENSE1_23") (pintype "open_collector"))
    )
    (net (code "75") (name "Net-(U1-SENSE2)") (class "Default")
      (node (ref "R18") (pin "1") (pinfunction "1_1") (pintype "passive"))
      (node (ref "U1") (pin "27") (pinfunction "SENSE2_27") (pintype "open_collector"))
    )
    (net (code "76") (name "Net-(U1-VCP)") (class "Default")
      (node (ref "C17") (pin "2") (pinfunction "2_2") (pintype "passive"))
      (node (ref "U1") (pin "6") (pinfunction "VCP_6") (pintype "open_collector"))
    )
    (net (code "77") (name "Net-(U1-VREG)") (class "Default")
      (node (ref "C21") (pin "1") (pinfunction "1_1") (pintype "passive"))
      (node (ref "U1") (pin "8") (pinfunction "VREG_8") (pintype "open_collector"))
    )
    (net (code "78") (name "Net-(U2-CP1)") (class "Default")
      (node (ref "C2") (pin "1") (pinfunction "1_1") (pintype "passive"))
      (node (ref "U2") (pin "4") (pinfunction "CP1_4") (pintype "open_collector"))
    )
    (net (code "79") (name "Net-(U2-CP2)") (class "Default")
      (node (ref "C2") (pin "2") (pinfunction "2_2") (pintype "passive"))
      (node (ref "U2") (pin "5") (pinfunction "CP2_5") (pintype "open_collector"))
    )
    (net (code "80") (name "Net-(U2-OUT1A)") (class "Default")
      (node (ref "U2") (pin "24") (pinfunction "OUT1A_24") (pintype "open_collector"))
      (node (ref "Y") (pin "2") (pinfunction "2_2") (pintype "passive"))
    )
    (net (code "81") (name "Net-(U2-OUT1B)") (class "Default")
      (node (ref "U2") (pin "21") (pinfunction "OUT1B_21") (pintype "open_collector"))
      (node (ref "Y") (pin "1") (pinfunction "1_1") (pintype "passive"))
    )
    (net (code "82") (name "Net-(U2-OUT2A)") (class "Default")
      (node (ref "U2") (pin "26") (pinfunction "OUT2A_26") (pintype "open_collector"))
      (node (ref "Y") (pin "3") (pinfunction "3_3") (pintype "passive"))
    )
    (net (code "83") (name "Net-(U2-OUT2B)") (class "Default")
      (node (ref "U2") (pin "1") (pinfunction "OUT2B_1") (pintype "open_collector"))
      (node (ref "Y") (pin "4") (pinfunction "4_4") (pintype "passive"))
    )
    (net (code "84") (name "Net-(U2-REF)") (class "Default")
      (node (ref "RP2") (pin "1") (pintype "passive"))
      (node (ref "U2") (pin "17") (pinfunction "REF_17") (pintype "open_collector"))
    )
    (net (code "85") (name "Net-(U2-RESET)") (class "Default")
      (node (ref "R2") (pin "1") (pinfunction "1_1") (pintype "passive"))
      (node (ref "U2") (pin "12") (pinfunction "RESET_12") (pintype "open_collector"))
      (node (ref "U2") (pin "14") (pinfunction "SLEEP_14") (pintype "open_collector"))
    )
    (net (code "86") (name "Net-(U2-ROSC)") (class "Default")
      (node (ref "R6") (pin "1") (pinfunction "1_1") (pintype "passive"))
      (node (ref "U2") (pin "13") (pinfunction "ROSC_13") (pintype "open_collector"))
    )
    (net (code "87") (name "Net-(U2-SENSE1)") (class "Default")
      (node (ref "R12") (pin "1") (pinfunction "1_1") (pintype "passive"))
      (node (ref "U2") (pin "23") (pinfunction "SENSE1_23") (pintype "open_collector"))
    )
    (net (code "88") (name "Net-(U2-SENSE2)") (class "Default")
      (node (ref "R20") (pin "1") (pinfunction "1_1") (pintype "passive"))
      (node (ref "U2") (pin "27") (pinfunction "SENSE2_27") (pintype "open_collector"))
    )
    (net (code "89") (name "Net-(U2-VCP)") (class "Default")
      (node (ref "C18") (pin "2") (pinfunction "2_2") (pintype "passive"))
      (node (ref "U2") (pin "6") (pinfunction "VCP_6") (pintype "open_collector"))
    )
    (net (code "90") (name "Net-(U2-VREG)") (class "Default")
      (node (ref "C22") (pin "1") (pinfunction "1_1") (pintype "passive"))
      (node (ref "U2") (pin "8") (pinfunction "VREG_8") (pintype "open_collector"))
    )
    (net (code "91") (name "Net-(U3-CP1)") (class "Default")
      (node (ref "C3") (pin "1") (pinfunction "1_1") (pintype "passive"))
      (node (ref "U3") (pin "4") (pinfunction "CP1_4") (pintype "open_collector"))
    )
    (net (code "92") (name "Net-(U3-CP2)") (class "Default")
      (node (ref "C3") (pin "2") (pinfunction "2_2") (pintype "passive"))
      (node (ref "U3") (pin "5") (pinfunction "CP2_5") (pintype "open_collector"))
    )
    (net (code "93") (name "Net-(U3-OUT1A)") (class "Default")
      (node (ref "U3") (pin "24") (pinfunction "OUT1A_24") (pintype "open_collector"))
      (node (ref "Z") (pin "2") (pinfunction "2_2") (pintype "passive"))
    )
    (net (code "94") (name "Net-(U3-OUT1B)") (class "Default")
      (node (ref "U3") (pin "21") (pinfunction "OUT1B_21") (pintype "open_collector"))
      (node (ref "Z") (pin "1") (pinfunction "1_1") (pintype "passive"))
    )
    (net (code "95") (name "Net-(U3-OUT2A)") (class "Default")
      (node (ref "U3") (pin "26") (pinfunction "OUT2A_26") (pintype "open_collector"))
      (node (ref "Z") (pin "3") (pinfunction "3_3") (pintype "passive"))
    )
    (net (code "96") (name "Net-(U3-OUT2B)") (class "Default")
      (node (ref "U3") (pin "1") (pinfunction "OUT2B_1") (pintype "open_collector"))
      (node (ref "Z") (pin "4") (pinfunction "4_4") (pintype "passive"))
    )
    (net (code "97") (name "Net-(U3-REF)") (class "Default")
      (node (ref "RP3") (pin "1") (pintype "passive"))
      (node (ref "U3") (pin "17") (pinfunction "REF_17") (pintype "open_collector"))
    )
    (net (code "98") (name "Net-(U3-RESET)") (class "Default")
      (node (ref "R3") (pin "1") (pinfunction "1_1") (pintype "passive"))
      (node (ref "U3") (pin "12") (pinfunction "RESET_12") (pintype "open_collector"))
      (node (ref "U3") (pin "14") (pinfunction "SLEEP_14") (pintype "open_collector"))
    )
    (net (code "99") (name "Net-(U3-ROSC)") (class "Default")
      (node (ref "R7") (pin "1") (pinfunction "1_1") (pintype "passive"))
      (node (ref "U3") (pin "13") (pinfunction "ROSC_13") (pintype "open_collector"))
    )
    (net (code "100") (name "Net-(U3-SENSE1)") (class "Default")
      (node (ref "R14") (pin "1") (pinfunction "1_1") (pintype "passive"))
      (node (ref "U3") (pin "23") (pinfunction "SENSE1_23") (pintype "open_collector"))
    )
    (net (code "101") (name "Net-(U3-SENSE2)") (class "Default")
      (node (ref "R22") (pin "1") (pinfunction "1_1") (pintype "passive"))
      (node (ref "U3") (pin "27") (pinfunction "SENSE2_27") (pintype "open_collector"))
    )
    (net (code "102") (name "Net-(U3-VCP)") (class "Default")
      (node (ref "C19") (pin "2") (pinfunction "2_2") (pintype "passive"))
      (node (ref "U3") (pin "6") (pinfunction "VCP_6") (pintype "open_collector"))
    )
    (net (code "103") (name "Net-(U3-VREG)") (class "Default")
      (node (ref "C23") (pin "1") (pinfunction "1_1") (pintype "passive"))
      (node (ref "U3") (pin "8") (pinfunction "VREG_8") (pintype "open_collector"))
    )
    (net (code "104") (name "Net-(U4-CP1)") (class "Default")
      (node (ref "C4") (pin "1") (pinfunction "1_1") (pintype "passive"))
      (node (ref "U4") (pin "4") (pinfunction "CP1_4") (pintype "open_collector"))
    )
    (net (code "105") (name "Net-(U4-CP2)") (class "Default")
      (node (ref "C4") (pin "2") (pinfunction "2_2") (pintype "passive"))
      (node (ref "U4") (pin "5") (pinfunction "CP2_5") (pintype "open_collector"))
    )
    (net (code "106") (name "Net-(U4-OUT1A)") (class "Default")
      (node (ref "E") (pin "2") (pinfunction "2_2") (pintype "passive"))
      (node (ref "U4") (pin "24") (pinfunction "OUT1A_24") (pintype "open_collector"))
    )
    (net (code "107") (name "Net-(U4-OUT1B)") (class "Default")
      (node (ref "E") (pin "1") (pinfunction "1_1") (pintype "passive"))
      (node (ref "U4") (pin "21") (pinfunction "OUT1B_21") (pintype "open_collector"))
    )
    (net (code "108") (name "Net-(U4-OUT2A)") (class "Default")
      (node (ref "E") (pin "3") (pinfunction "3_3") (pintype "passive"))
      (node (ref "U4") (pin "26") (pinfunction "OUT2A_26") (pintype "open_collector"))
    )
    (net (code "109") (name "Net-(U4-OUT2B)") (class "Default")
      (node (ref "E") (pin "4") (pinfunction "4_4") (pintype "passive"))
      (node (ref "U4") (pin "1") (pinfunction "OUT2B_1") (pintype "open_collector"))
    )
    (net (code "110") (name "Net-(U4-REF)") (class "Default")
      (node (ref "RP4") (pin "1") (pintype "passive"))
      (node (ref "U4") (pin "17") (pinfunction "REF_17") (pintype "open_collector"))
    )
    (net (code "111") (name "Net-(U4-RESET)") (class "Default")
      (node (ref "R4") (pin "1") (pinfunction "1_1") (pintype "passive"))
      (node (ref "U4") (pin "12") (pinfunction "RESET_12") (pintype "open_collector"))
      (node (ref "U4") (pin "14") (pinfunction "SLEEP_14") (pintype "open_collector"))
    )
    (net (code "112") (name "Net-(U4-ROSC)") (class "Default")
      (node (ref "R8") (pin "1") (pinfunction "1_1") (pintype "passive"))
      (node (ref "U4") (pin "13") (pinfunction "ROSC_13") (pintype "open_collector"))
    )
    (net (code "113") (name "Net-(U4-SENSE1)") (class "Default")
      (node (ref "R16") (pin "1") (pinfunction "1_1") (pintype "passive"))
      (node (ref "U4") (pin "23") (pinfunction "SENSE1_23") (pintype "open_collector"))
    )
    (net (code "114") (name "Net-(U4-SENSE2)") (class "Default")
      (node (ref "R24") (pin "1") (pinfunction "1_1") (pintype "passive"))
      (node (ref "U4") (pin "27") (pinfunction "SENSE2_27") (pintype "open_collector"))
    )
    (net (code "115") (name "Net-(U4-VCP)") (class "Default")
      (node (ref "C20") (pin "2") (pinfunction "2_2") (pintype "passive"))
      (node (ref "U4") (pin "6") (pinfunction "VCP_6") (pintype "open_collector"))
    )
    (net (code "116") (name "Net-(U4-VREG)") (class "Default")
      (node (ref "C24") (pin "1") (pinfunction "1_1") (pintype "passive"))
      (node (ref "U4") (pin "8") (pinfunction "VREG_8") (pintype "open_collector"))
    )
    (net (code "117") (name "Net-(U5-BOOT0)") (class "Default")
      (node (ref "R31") (pin "1") (pinfunction "1_1") (pintype "passive"))
      (node (ref "U5") (pin "60") (pinfunction "BOOT0_60") (pintype "passive"))
    )
    (net (code "118") (name "Net-(U5-OSC_IN)") (class "Default")
      (node (ref "C33") (pin "2") (pinfunction "2_2") (pintype "passive"))
      (node (ref "U5") (pin "5") (pinfunction "OSC_IN_5") (pintype "passive"))
      (node (ref "Y2") (pin "1") (pinfunction "OSC2_1") (pintype "passive"))
    )
    (net (code "119") (name "Net-(U5-OSC_OUT)") (class "Default")
      (node (ref "C34") (pin "2") (pinfunction "2_2") (pintype "passive"))
      (node (ref "U5") (pin "6") (pinfunction "OSC_OUT_6") (pintype "passive"))
      (node (ref "Y2") (pin "2") (pinfunction "OSC1_2") (pintype "passive"))
    )
    (net (code "120") (name "Net-(U5-VDDA)") (class "Default")
      (node (ref "C35") (pin "1") (pinfunction "1_1") (pintype "passive"))
      (node (ref "C36") (pin "1") (pinfunction "1_1") (pintype "passive"))
      (node (ref "R33") (pin "1") (pinfunction "1_1") (pintype "passive"))
      (node (ref "U5") (pin "13") (pinfunction "VDDA_13") (pintype "passive"))
    )
    (net (code "121") (name "Net-(U5-VSSA)") (class "Default")
      (node (ref "R34") (pin "2") (pinfunction "2_2") (pintype "passive"))
      (node (ref "U5") (pin "12") (pinfunction "VSSA_12") (pintype "passive"))
    )
    (net (code "122") (name "Net-(U6-BST)") (class "Default")
      (node (ref "C25") (pin "2") (pinfunction "2_2") (pintype "passive"))
      (node (ref "U6") (pin "8") (pinfunction "BST_8") (pintype "passive"))
    )
    (net (code "123") (name "Net-(U6-COMP)") (class "Default")
      (node (ref "C32") (pin "1") (pinfunction "1_1") (pintype "passive"))
      (node (ref "U6") (pin "3") (pinfunction "COMP_3") (pintype "passive"))
    )
    (net (code "124") (name "Net-(U6-EN)") (class "Default")
      (node (ref "R26") (pin "2") (pinfunction "2_2") (pintype "passive"))
      (node (ref "U6") (pin "2") (pinfunction "EN_2") (pintype "passive"))
    )
    (net (code "125") (name "Net-(U6-FB)") (class "Default")
      (node (ref "R27") (pin "1") (pinfunction "1_1") (pintype "passive"))
      (node (ref "R29") (pin "2") (pinfunction "2_2") (pintype "passive"))
      (node (ref "U6") (pin "4") (pinfunction "FB_4") (pintype "passive"))
    )
    (net (code "126") (name "Net-(U6-FREQ)") (class "Default")
      (node (ref "R28") (pin "2") (pinfunction "2_2") (pintype "passive"))
      (node (ref "U6") (pin "6") (pinfunction "FREQ_6") (pintype "passive"))
    )
    (net (code "127") (name "Net-(U7-DTR)") (class "Default")
      (node (ref "C43") (pin "2") (pinfunction "2_2") (pintype "passive"))
      (node (ref "U7") (pin "13") (pinfunction "DTR_13") (pintype "open_collector"))
    )
    (net (code "128") (name "Net-(U7-XI)") (class "Default")
      (node (ref "U7") (pin "7") (pinfunction "XI_7") (pintype "open_collector"))
      (node (ref "Y3") (pin "3") (pinfunction "3_3") (pintype "passive"))
    )
    (net (code "129") (name "Net-(U7-XO)") (class "Default")
      (node (ref "U7") (pin "8") (pinfunction "XO_8") (pintype "open_collector"))
      (node (ref "Y3") (pin "1") (pinfunction "1_1") (pintype "passive"))
    )
    (net (code "130") (name "Net-(U8-BOOT)") (class "Default")
      (node (ref "C29") (pin "2") (pinfunction "2_2") (pintype "passive"))
      (node (ref "U8") (pin "1") (pinfunction "BOOT_1") (pintype "passive"))
    )
    (net (code "131") (name "Net-(U8-PH)") (class "Default")
      (node (ref "C29") (pin "1") (pinfunction "1_1") (pintype "passive"))
      (node (ref "D8") (pin "K") (pinfunction "K_K") (pintype "passive"))
      (node (ref "L3") (pin "1") (pinfunction "1_1") (pintype "passive"))
      (node (ref "U8") (pin "8") (pinfunction "PH_8") (pintype "passive"))
    )
    (net (code "132") (name "Net-(U8-VSENSE)") (class "Default")
      (node (ref "R56") (pin "1") (pinfunction "1_1") (pintype "passive"))
      (node (ref "R57") (pin "2") (pinfunction "2_2") (pintype "passive"))
      (node (ref "U8") (pin "4") (pinfunction "VSENSE_4") (pintype "passive"))
    )
    (net (code "133") (name "Net-(U9-P3.0{slash}~{INT4}{slash}T2CLKO)") (class "Default")
      (node (ref "J1") (pin "2") (pinfunction "2_2") (pintype "passive"))
      (node (ref "R54") (pin "1") (pinfunction "1_1") (pintype "passive"))
      (node (ref "U9") (pin "5") (pinfunction "P3.0/~{INT4}/T2CLKO_5") (pintype "passive"))
    )
    (net (code "134") (name "Net-(U9-P3.1{slash}T2)") (class "Default")
      (node (ref "J1") (pin "1") (pinfunction "1_1") (pintype "passive"))
      (node (ref "R55") (pin "1") (pinfunction "1_1") (pintype "passive"))
      (node (ref "U9") (pin "6") (pinfunction "P3.1/T2_6") (pintype "passive"))
    )
    (net (code "135") (name "VIN") (class "Default")
      (node (ref "C10") (pin "1") (pinfunction "1_1") (pintype "passive"))
      (node (ref "C11") (pin "1") (pinfunction "1_1") (pintype "passive"))
      (node (ref "C12") (pin "1") (pinfunction "1_1") (pintype "passive"))
      (node (ref "C13") (pin "1") (pinfunction "1_1") (pintype "passive"))
      (node (ref "C14") (pin "1") (pinfunction "1_1") (pintype "passive"))
      (node (ref "C15") (pin "1") (pinfunction "1_1") (pintype "passive"))
      (node (ref "C16") (pin "1") (pinfunction "1_1") (pintype "passive"))
      (node (ref "C17") (pin "1") (pinfunction "1_1") (pintype "passive"))
      (node (ref "C18") (pin "1") (pinfunction "1_1") (pintype "passive"))
      (node (ref "C19") (pin "1") (pinfunction "1_1") (pintype "passive"))
      (node (ref "C20") (pin "1") (pinfunction "1_1") (pintype "passive"))
      (node (ref "C30") (pin "1") (pinfunction "1_1") (pintype "passive"))
      (node (ref "C31") (pin "1") (pinfunction "1_1") (pintype "passive"))
      (node (ref "C5") (pin "1") (pinfunction "1_1") (pintype "passive"))
      (node (ref "C6") (pin "1") (pinfunction "1_1") (pintype "passive"))
      (node (ref "C7") (pin "1") (pinfunction "1_1") (pintype "passive"))
      (node (ref "C8") (pin "1") (pinfunction "1_1") (pintype "passive"))
      (node (ref "C9") (pin "1") (pinfunction "1_1") (pintype "passive"))
      (node (ref "D2") (pin "2") (pinfunction "K_2") (pintype "passive"))
      (node (ref "F1") (pin "2") (pinfunction "2_2") (pintype "passive"))
      (node (ref "FAN1") (pin "1") (pinfunction "1_1") (pintype "passive"))
      (node (ref "FAN2") (pin "1") (pinfunction "1_1") (pintype "passive"))
      (node (ref "HEATER1") (pin "1") (pinfunction "1_1") (pintype "passive"))
      (node (ref "R26") (pin "1") (pinfunction "1_1") (pintype "passive"))
      (node (ref "R45") (pin "1") (pinfunction "1_1") (pintype "passive"))
      (node (ref "TH1") (pin "1") (pinfunction "1_1") (pintype "passive"))
      (node (ref "U1") (pin "22") (pinfunction "VBB1_22") (pintype "open_collector"))
      (node (ref "U1") (pin "28") (pinfunction "VBB2_28") (pintype "open_collector"))
      (node (ref "U2") (pin "22") (pinfunction "VBB1_22") (pintype "open_collector"))
      (node (ref "U2") (pin "28") (pinfunction "VBB2_28") (pintype "open_collector"))
      (node (ref "U3") (pin "22") (pinfunction "VBB1_22") (pintype "open_collector"))
      (node (ref "U3") (pin "28") (pinfunction "VBB2_28") (pintype "open_collector"))
      (node (ref "U4") (pin "22") (pinfunction "VBB1_22") (pintype "open_collector"))
      (node (ref "U4") (pin "28") (pinfunction "VBB2_28") (pintype "open_collector"))
      (node (ref "U6") (pin "7") (pinfunction "VIN_7") (pintype "passive"))
    )
    (net (code "136") (name "unconnected-(D3-K-Pad2)") (class "Default")
      (node (ref "D3") (pin "2") (pinfunction "K_2") (pintype "passive"))
    )
    (net (code "137") (name "unconnected-(JK1-Pad5)") (class "Default")
      (node (ref "JK1") (pin "5") (pinfunction "5_5") (pintype "passive"))
    )
    (net (code "138") (name "unconnected-(U5-PA0-WKUP{slash}USART2_CTS{slash}ADC123_IN0{slash}TIM5_CH1{slash}TIM2_CH1_ETR{slash}TIM8_ETR-Pad14)") (class "Default")
      (node (ref "U5") (pin "14") (pinfunction "PA0-WKUP/USART2_CTS/ADC123_IN0/TIM5_CH1/TIM2_CH1_ETR/TIM8_ETR_14") (pintype "passive"))
    )
    (net (code "139") (name "unconnected-(U5-PA2{slash}USART2_TX{slash}ADC123_IN2{slash}TIM5_CH3{slash}TIM2_CH3-Pad16)") (class "Default")
      (node (ref "U5") (pin "16") (pinfunction "PA2/USART2_TX/ADC123_IN2/TIM5_CH3/TIM2_CH3_16") (pintype "passive"))
    )
    (net (code "140") (name "unconnected-(U5-PA3{slash}USART2_RX{slash}ADC123_IN3{slash}TIM5_CH4{slash}TIM2_CH4-Pad17)") (class "Default")
      (node (ref "U5") (pin "17") (pinfunction "PA3/USART2_RX/ADC123_IN3/TIM5_CH4/TIM2_CH4_17") (pintype "passive"))
    )
    (net (code "141") (name "unconnected-(U5-PA4{slash}SPI1_NSS{slash}DAC_OUT1{slash}USART2_CK{slash}ADC12_IN4-Pad20)") (class "Default")
      (node (ref "U5") (pin "20") (pinfunction "PA4/SPI1_NSS/DAC_OUT1/USART2_CK/ADC12_IN4_20") (pintype "passive"))
    )
    (net (code "142") (name "unconnected-(U5-PA11{slash}USART1_CTS{slash}CAN_RX{slash}TIM1_CH4{slash}USBDM-Pad44)") (class "Default")
      (node (ref "U5") (pin "44") (pinfunction "PA11/USART1_CTS/CAN_RX/TIM1_CH4/USBDM_44") (pintype "passive"))
    )
    (net (code "143") (name "unconnected-(U5-PA12{slash}USART1_RTS{slash}CAN_TX{slash}TIM1_ETR{slash}USBDP-Pad45)") (class "Default")
      (node (ref "U5") (pin "45") (pinfunction "PA12/USART1_RTS/CAN_TX/TIM1_ETR/USBDP_45") (pintype "passive"))
    )
    (net (code "144") (name "unconnected-(U5-PC4{slash}ADC12_IN14-Pad24)") (class "Default")
      (node (ref "U5") (pin "24") (pinfunction "PC4/ADC12_IN14_24") (pintype "passive"))
    )
    (net (code "145") (name "unconnected-(U5-PC5{slash}ADC12_IN15-Pad25)") (class "Default")
      (node (ref "U5") (pin "25") (pinfunction "PC5/ADC12_IN15_25") (pintype "passive"))
    )
    (net (code "146") (name "unconnected-(U5-PC13{slash}TAMPER-RTC-Pad2)") (class "Default")
      (node (ref "U5") (pin "2") (pinfunction "PC13/TAMPER-RTC_2") (pintype "passive+no_connect"))
    )
    (net (code "147") (name "unconnected-(U5-PC14{slash}OSC32_IN-Pad3)") (class "Default")
      (node (ref "U5") (pin "3") (pinfunction "PC14/OSC32_IN_3") (pintype "passive+no_connect"))
    )
    (net (code "148") (name "unconnected-(U5-PC15{slash}OSC32_OUT-Pad4)") (class "Default")
      (node (ref "U5") (pin "4") (pinfunction "PC15/OSC32_OUT_4") (pintype "passive+no_connect"))
    )
    (net (code "149") (name "unconnected-(U5-VBAT-Pad1)") (class "Default")
      (node (ref "U5") (pin "1") (pinfunction "VBAT_1") (pintype "passive+no_connect"))
    )
    (net (code "150") (name "unconnected-(U7-CTS-Pad9)") (class "Default")
      (node (ref "U7") (pin "9") (pinfunction "CTS_9") (pintype "open_collector"))
    )
    (net (code "151") (name "unconnected-(U7-DCD-Pad12)") (class "Default")
      (node (ref "U7") (pin "12") (pinfunction "DCD_12") (pintype "open_collector"))
    )
    (net (code "152") (name "unconnected-(U7-DSR-Pad10)") (class "Default")
      (node (ref "U7") (pin "10") (pinfunction "DSR_10") (pintype "open_collector"))
    )
    (net (code "153") (name "unconnected-(U7-R232-Pad15)") (class "Default")
      (node (ref "U7") (pin "15") (pinfunction "R232_15") (pintype "open_collector"))
    )
    (net (code "154") (name "unconnected-(U7-RI-Pad11)") (class "Default")
      (node (ref "U7") (pin "11") (pinfunction "RI_11") (pintype "open_collector"))
    )
    (net (code "155") (name "unconnected-(U7-RTS-Pad14)") (class "Default")
      (node (ref "U7") (pin "14") (pinfunction "RTS_14") (pintype "open_collector"))
    )
    (net (code "156") (name "unconnected-(U8-ENA-Pad5)") (class "Default")
      (node (ref "U8") (pin "5") (pinfunction "ENA_5") (pintype "passive+no_connect"))
    )
    (net (code "157") (name "unconnected-(U8-NC-Pad2)") (class "Default")
      (node (ref "U8") (pin "2") (pinfunction "NC_2") (pintype "passive+no_connect"))
    )
    (net (code "158") (name "unconnected-(U8-NC-Pad3)") (class "Default")
      (node (ref "U8") (pin "3") (pinfunction "NC_3") (pintype "passive+no_connect"))
    )
    (net (code "159") (name "unconnected-(U9-P3.4{slash}RST{slash}T0{slash}~{INT2}{slash}MCLKO-Pad1)") (class "Default")
      (node (ref "U9") (pin "1") (pinfunction "P3.4/RST/T0/~{INT2}/MCLKO_1") (pintype "passive+no_connect"))
    )
    (net (code "160") (name "unconnected-(U9-P3.5{slash}T0CLKO{slash}~{INT3}-Pad3)") (class "Default")
      (node (ref "U9") (pin "3") (pinfunction "P3.5/T0CLKO/~{INT3}_3") (pintype "passive+no_connect"))
    )
    (net (code "161") (name "unconnected-(USB1-Pad2)") (class "Default")
      (node (ref "USB1") (pin "2") (pinfunction "2_2") (pintype "passive"))
    )
  )
)
